# VU-Meter.net
KiCad netlist of a schematic drawn in EAGLE
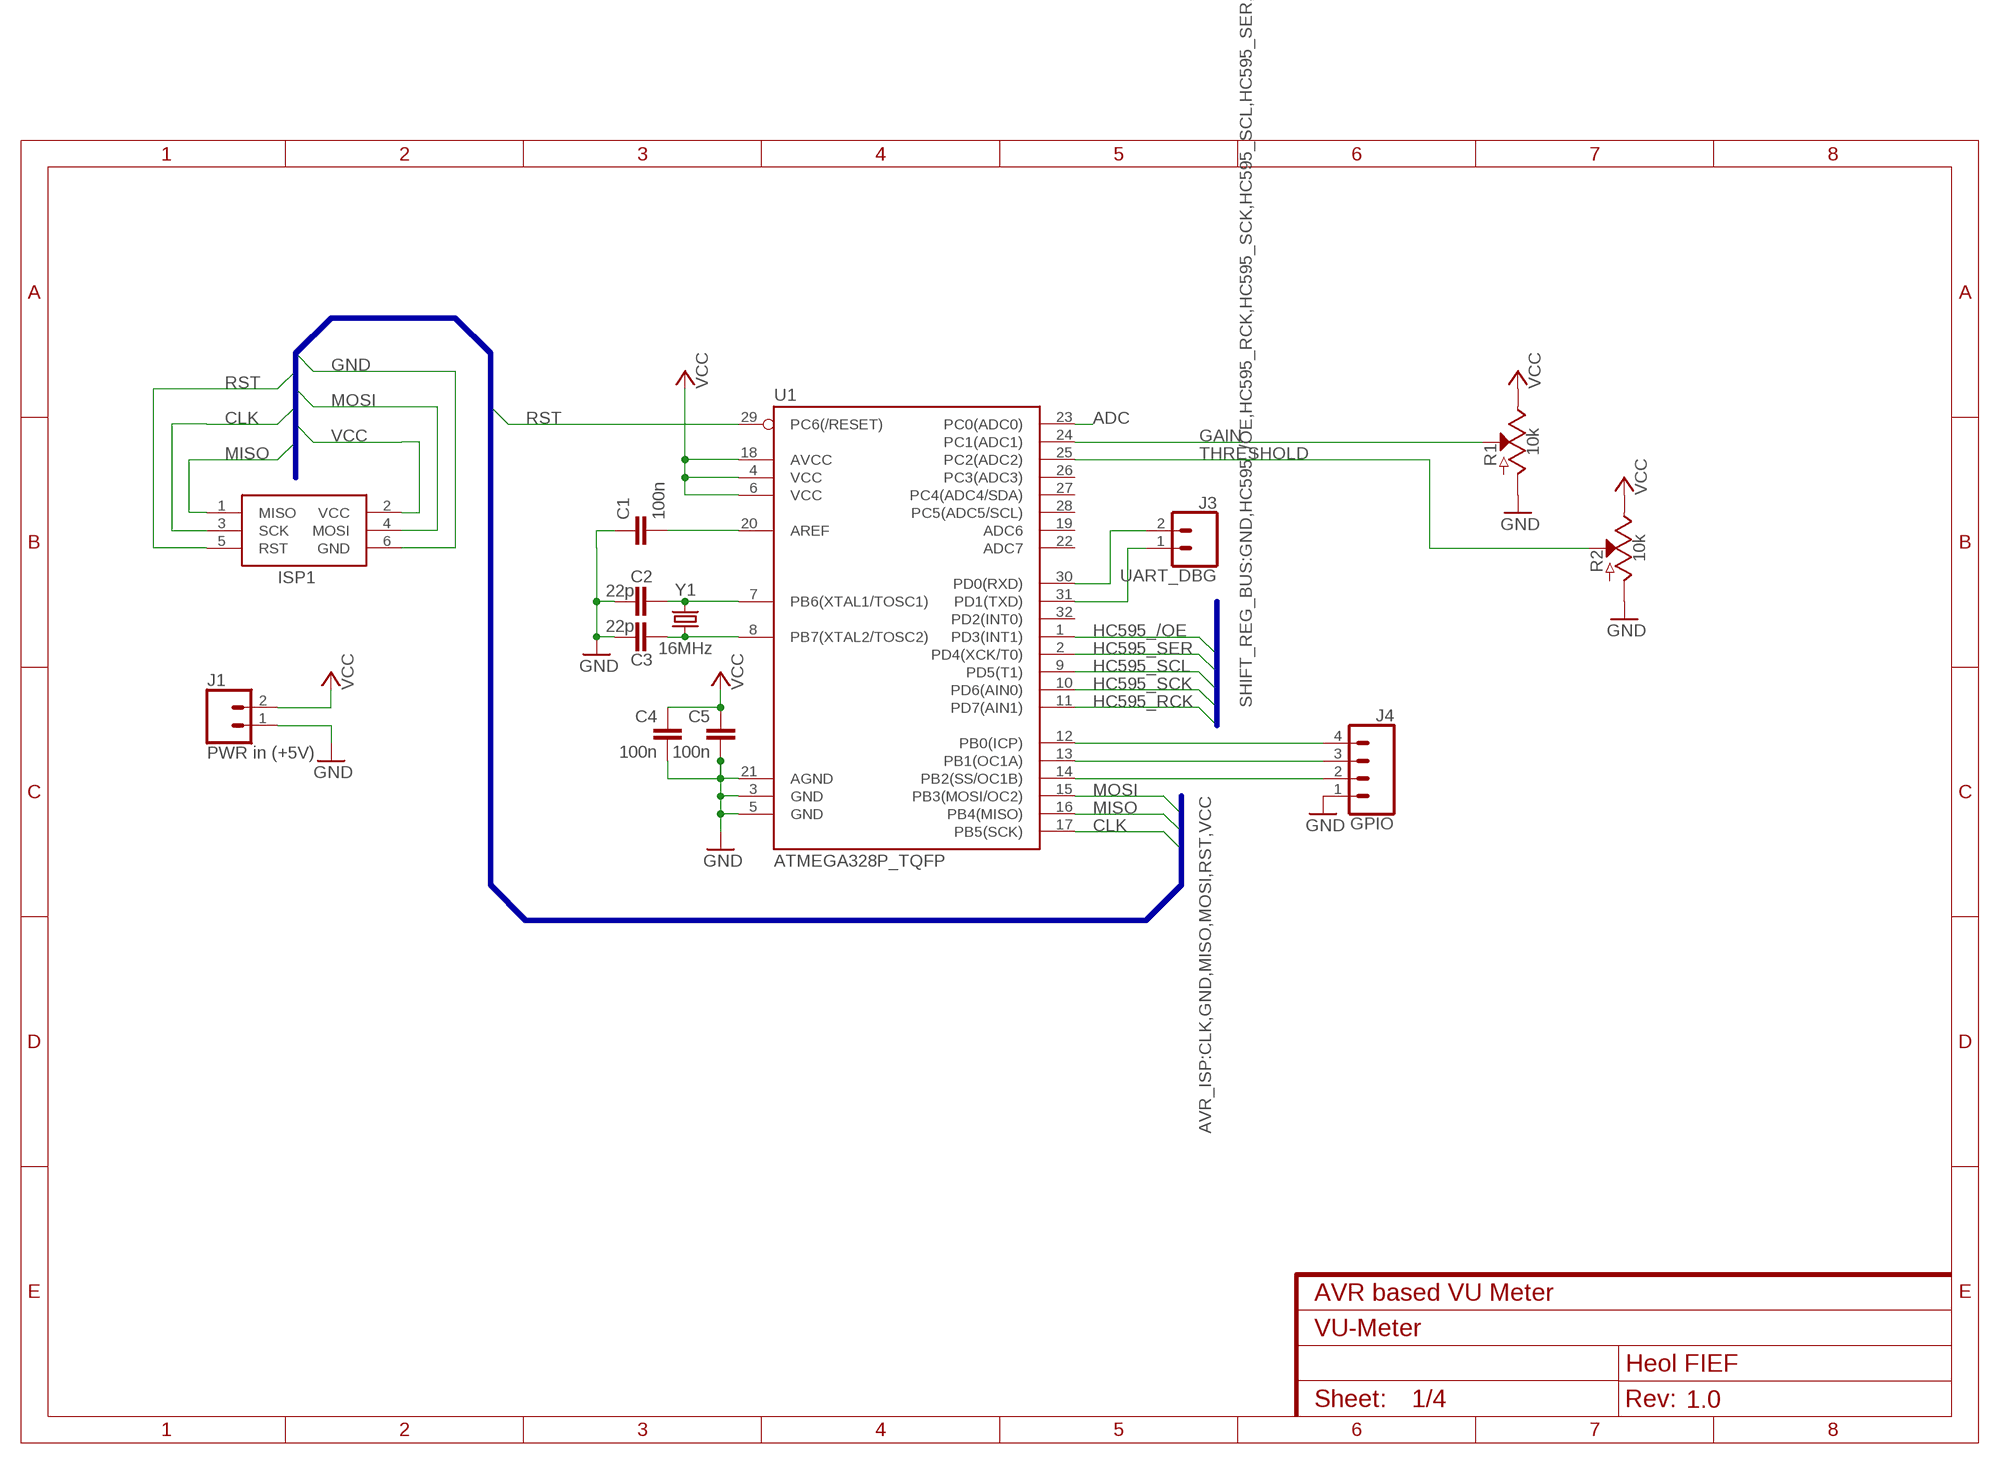
[diagram p0: schematic, sheet 1]
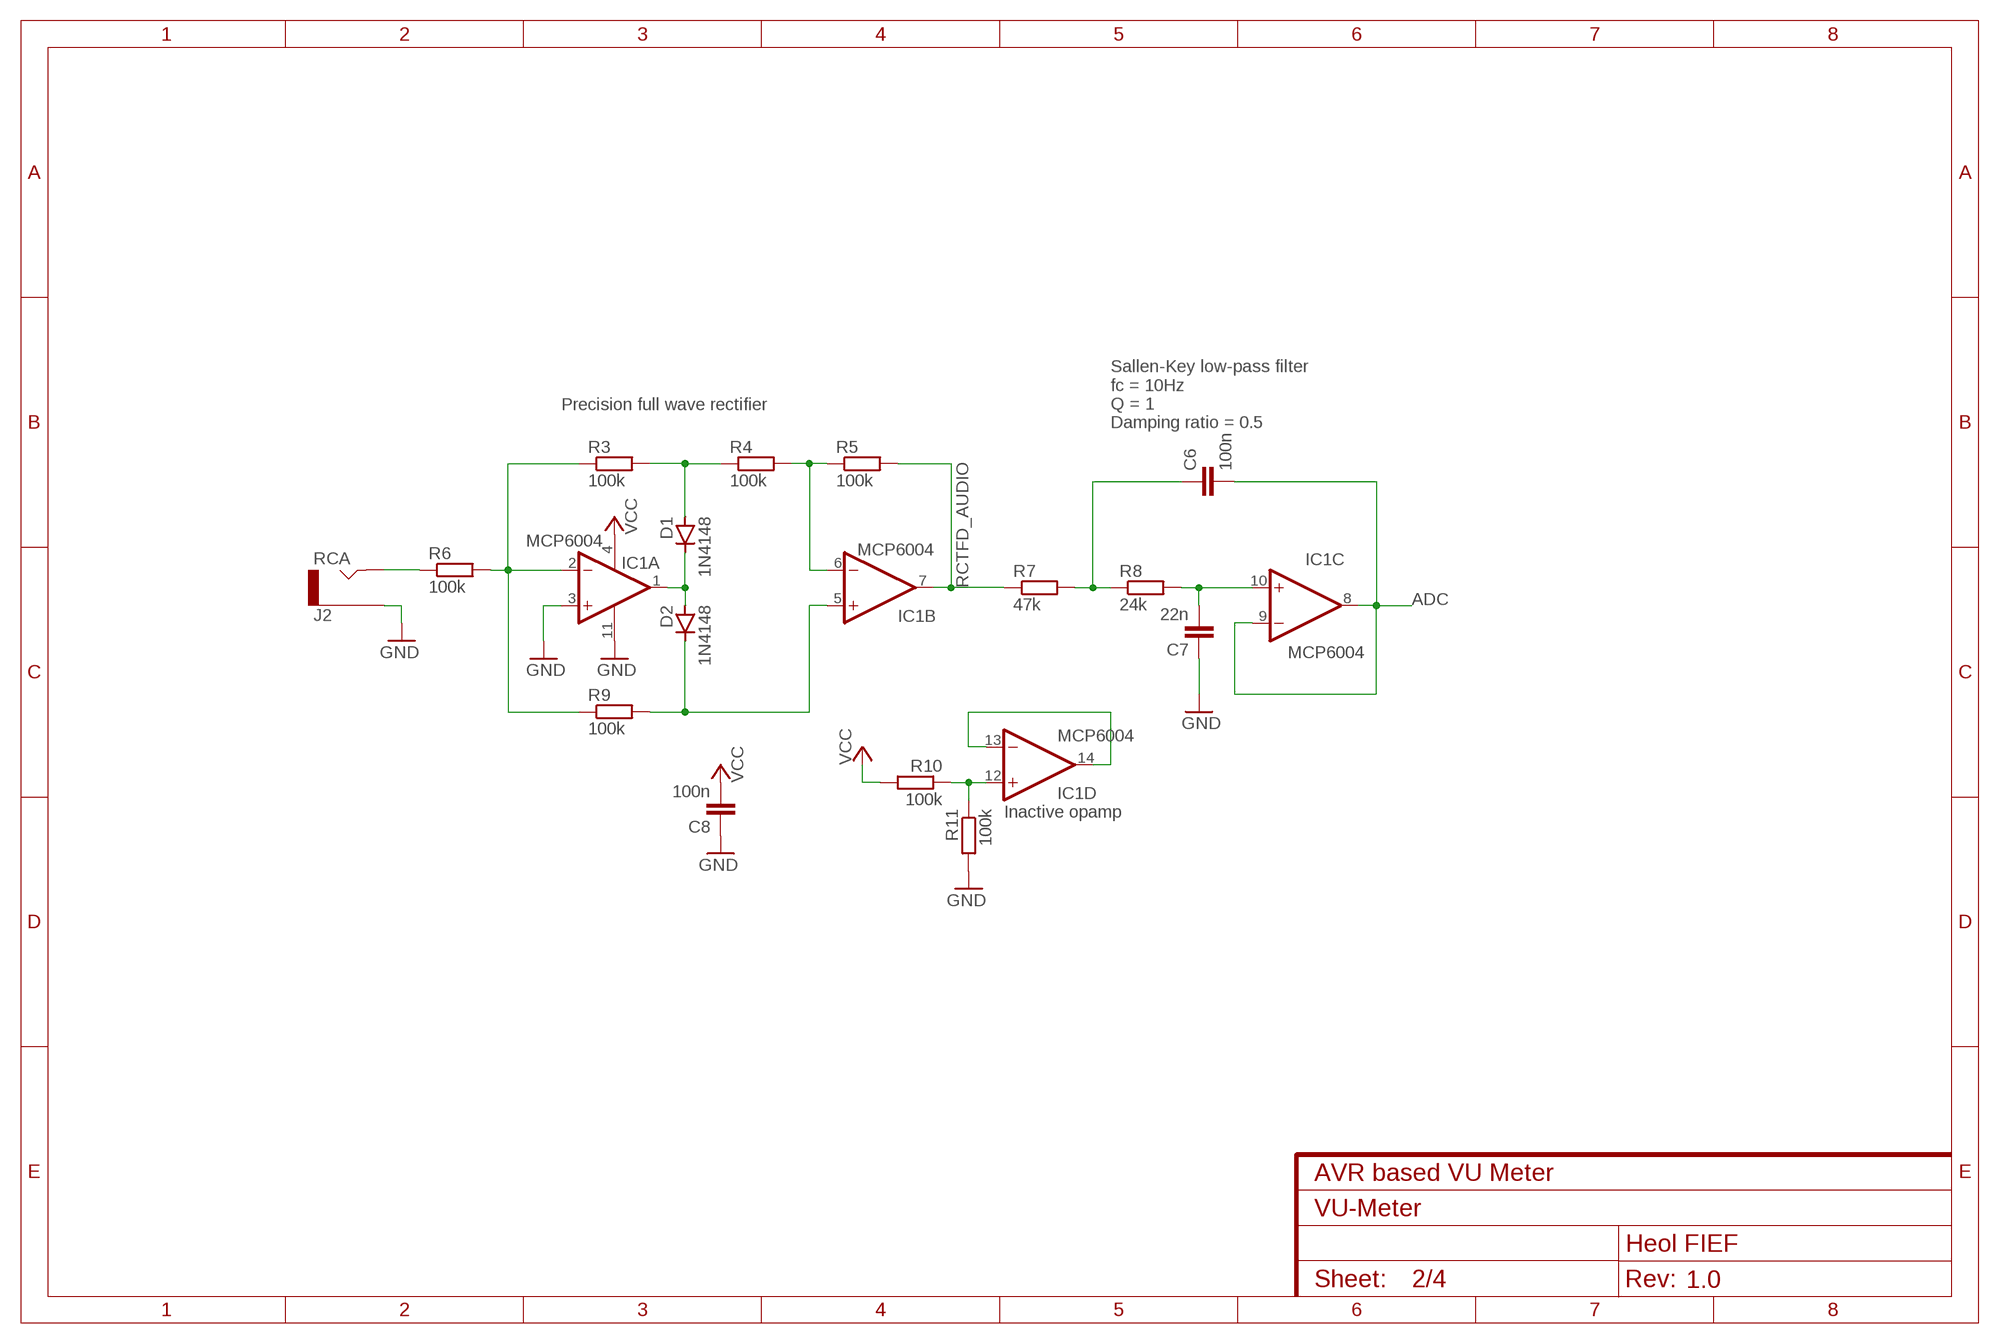
[diagram p1: schematic, sheet 2]
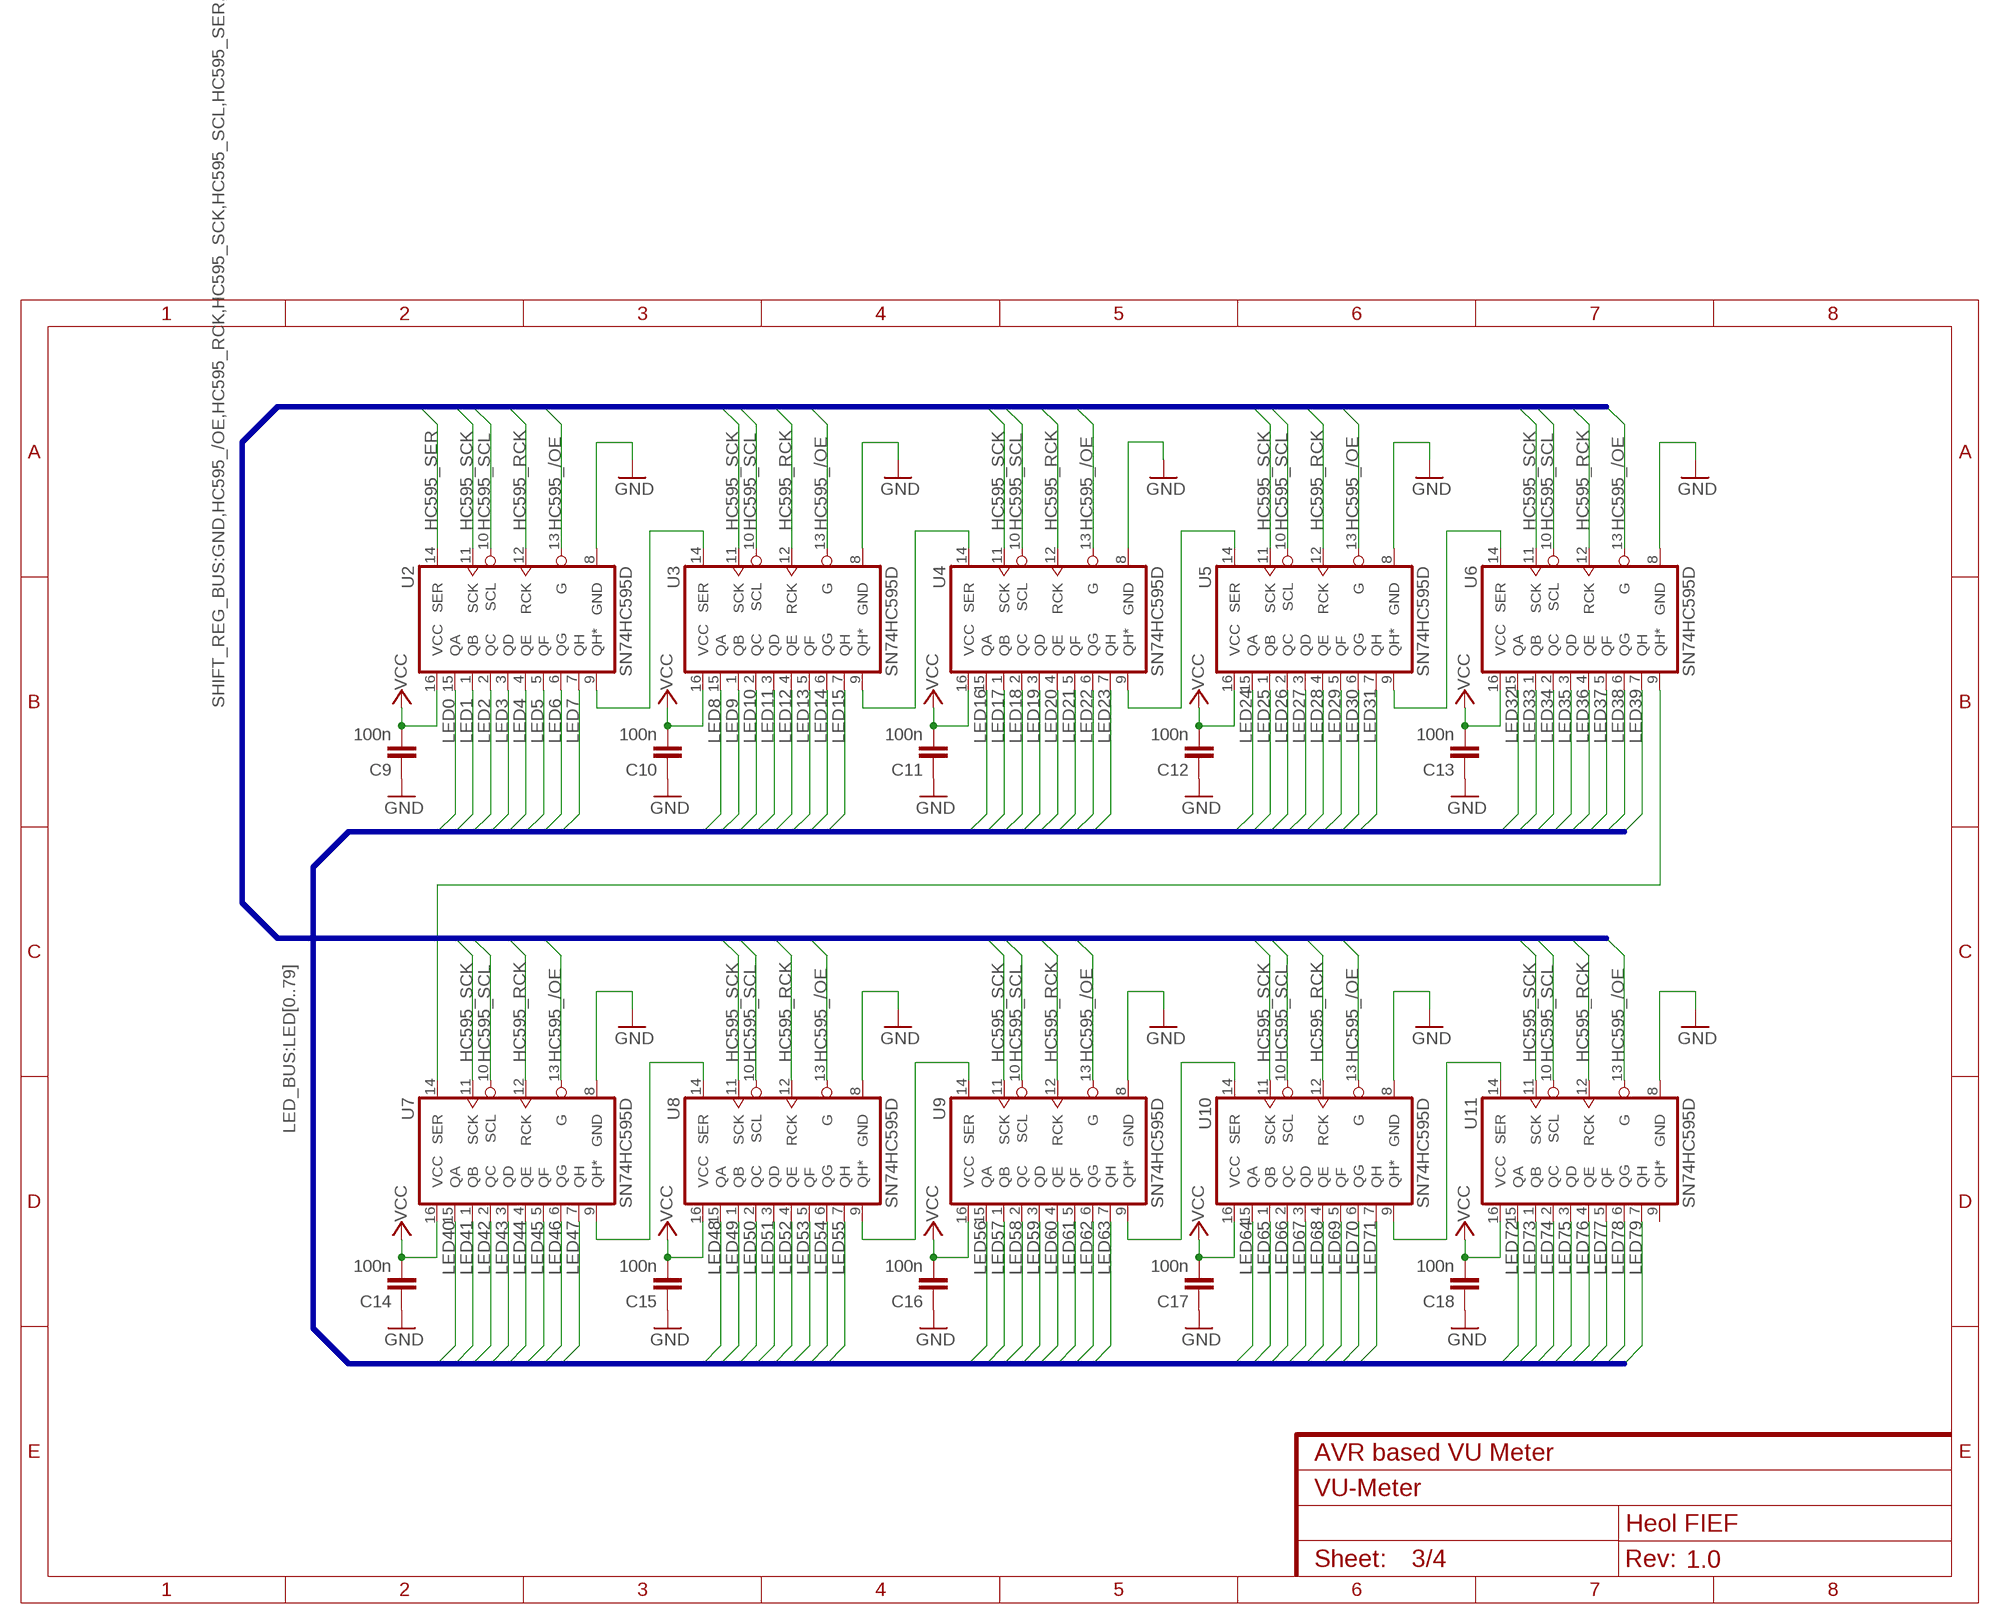
[diagram p2: schematic, sheet 3]
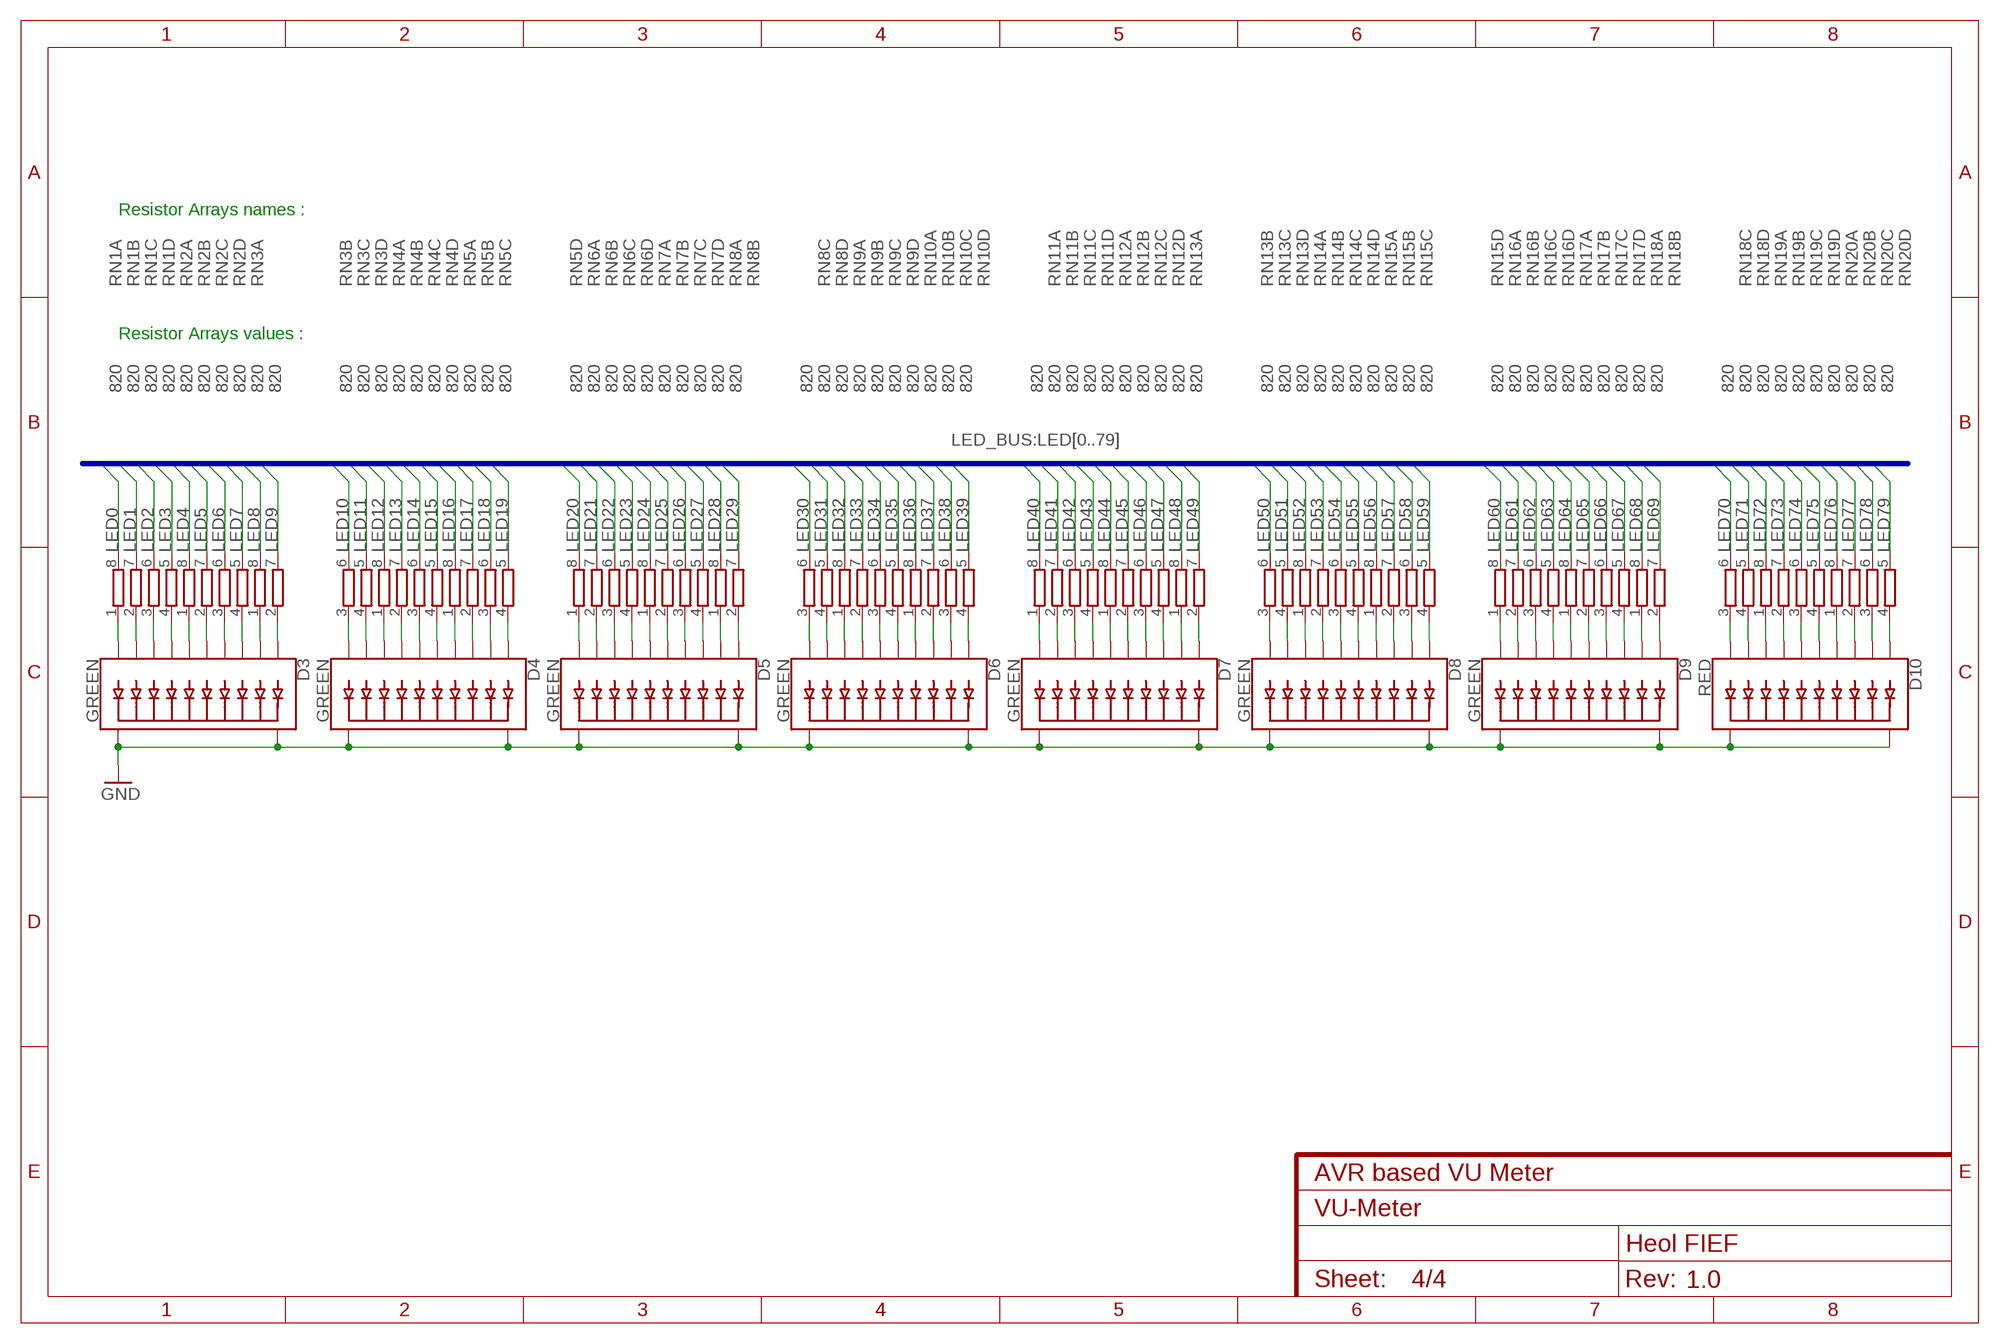
[diagram p3: schematic, sheet 4]

(export (version "E")
  (design (tool "Eeschema 10.0.6"))
  (components
    (comp (ref "C9")
      (value "100n")
      (footprint "eagle-import:C0805")
      (libsource (lib "eagle-import") (part "C-EUC0805"))
    )
    (comp (ref "C10")
      (value "100n")
      (footprint "eagle-import:C0805")
      (libsource (lib "eagle-import") (part "C-EUC0805"))
    )
    (comp (ref "C11")
      (value "100n")
      (footprint "eagle-import:C0805")
      (libsource (lib "eagle-import") (part "C-EUC0805"))
    )
    (comp (ref "C12")
      (value "100n")
      (footprint "eagle-import:C0805")
      (libsource (lib "eagle-import") (part "C-EUC0805"))
    )
    (comp (ref "C13")
      (value "100n")
      (footprint "eagle-import:C0805")
      (libsource (lib "eagle-import") (part "C-EUC0805"))
    )
    (comp (ref "C14")
      (value "100n")
      (footprint "eagle-import:C0805")
      (libsource (lib "eagle-import") (part "C-EUC0805"))
    )
    (comp (ref "C15")
      (value "100n")
      (footprint "eagle-import:C0805")
      (libsource (lib "eagle-import") (part "C-EUC0805"))
    )
    (comp (ref "C16")
      (value "100n")
      (footprint "eagle-import:C0805")
      (libsource (lib "eagle-import") (part "C-EUC0805"))
    )
    (comp (ref "C17")
      (value "100n")
      (footprint "eagle-import:C0805")
      (libsource (lib "eagle-import") (part "C-EUC0805"))
    )
    (comp (ref "C18")
      (value "100n")
      (footprint "eagle-import:C0805")
      (libsource (lib "eagle-import") (part "C-EUC0805"))
    )
    (comp (ref "U2")
      (value "SN74HC595D")
      (footprint "eagle-import:SO16")
      (libsource (lib "eagle-import") (part "74595DHC"))
    )
    (comp (ref "U3")
      (value "SN74HC595D")
      (footprint "eagle-import:SO16")
      (libsource (lib "eagle-import") (part "74595DHC"))
    )
    (comp (ref "U4")
      (value "SN74HC595D")
      (footprint "eagle-import:SO16")
      (libsource (lib "eagle-import") (part "74595DHC"))
    )
    (comp (ref "U5")
      (value "SN74HC595D")
      (footprint "eagle-import:SO16")
      (libsource (lib "eagle-import") (part "74595DHC"))
    )
    (comp (ref "U6")
      (value "SN74HC595D")
      (footprint "eagle-import:SO16")
      (libsource (lib "eagle-import") (part "74595DHC"))
    )
    (comp (ref "U7")
      (value "SN74HC595D")
      (footprint "eagle-import:SO16")
      (libsource (lib "eagle-import") (part "74595DHC"))
    )
    (comp (ref "U8")
      (value "SN74HC595D")
      (footprint "eagle-import:SO16")
      (libsource (lib "eagle-import") (part "74595DHC"))
    )
    (comp (ref "U9")
      (value "SN74HC595D")
      (footprint "eagle-import:SO16")
      (libsource (lib "eagle-import") (part "74595DHC"))
    )
    (comp (ref "U10")
      (value "SN74HC595D")
      (footprint "eagle-import:SO16")
      (libsource (lib "eagle-import") (part "74595DHC"))
    )
    (comp (ref "U11")
      (value "SN74HC595D")
      (footprint "eagle-import:SO16")
      (libsource (lib "eagle-import") (part "74595DHC"))
    )
    (comp (ref "D3")
      (value "GREEN")
      (footprint "eagle-import:LED_BARGRAPH_OFFBOARD_RIGHT_ANGLE")
      (libsource (lib "eagle-import") (part "LED_BARGRAPH_OFFBOARDLED_BARGRAPH_OFFBOARD"))
    )
    (comp (ref "D4")
      (value "GREEN")
      (footprint "eagle-import:LED_BARGRAPH_OFFBOARD_RIGHT_ANGLE")
      (libsource (lib "eagle-import") (part "LED_BARGRAPH_OFFBOARDLED_BARGRAPH_OFFBOARD"))
    )
    (comp (ref "D5")
      (value "GREEN")
      (footprint "eagle-import:LED_BARGRAPH_OFFBOARD_RIGHT_ANGLE")
      (libsource (lib "eagle-import") (part "LED_BARGRAPH_OFFBOARDLED_BARGRAPH_OFFBOARD"))
    )
    (comp (ref "D6")
      (value "GREEN")
      (footprint "eagle-import:LED_BARGRAPH_OFFBOARD_RIGHT_ANGLE")
      (libsource (lib "eagle-import") (part "LED_BARGRAPH_OFFBOARDLED_BARGRAPH_OFFBOARD"))
    )
    (comp (ref "D7")
      (value "GREEN")
      (footprint "eagle-import:LED_BARGRAPH_OFFBOARD_RIGHT_ANGLE")
      (libsource (lib "eagle-import") (part "LED_BARGRAPH_OFFBOARDLED_BARGRAPH_OFFBOARD"))
    )
    (comp (ref "D8")
      (value "GREEN")
      (footprint "eagle-import:LED_BARGRAPH_OFFBOARD_RIGHT_ANGLE")
      (libsource (lib "eagle-import") (part "LED_BARGRAPH_OFFBOARDLED_BARGRAPH_OFFBOARD"))
    )
    (comp (ref "D9")
      (value "GREEN")
      (footprint "eagle-import:LED_BARGRAPH_OFFBOARD_RIGHT_ANGLE")
      (libsource (lib "eagle-import") (part "LED_BARGRAPH_OFFBOARDLED_BARGRAPH_OFFBOARD"))
    )
    (comp (ref "D10")
      (value "RED")
      (footprint "eagle-import:LED_BARGRAPH_OFFBOARD_RIGHT_ANGLE")
      (libsource (lib "eagle-import") (part "LED_BARGRAPH_OFFBOARDLED_BARGRAPH_OFFBOARD"))
    )
    (comp (ref "RN1")
      (value "820")
      (footprint "eagle-import:0603-ARC")
      (libsource (lib "eagle-import") (part "4R-N0603-ARC"))
    )
    (comp (ref "RN2")
      (value "820")
      (footprint "eagle-import:0603-ARC")
      (libsource (lib "eagle-import") (part "4R-N0603-ARC"))
    )
    (comp (ref "RN3")
      (value "820")
      (footprint "eagle-import:0603-ARC")
      (libsource (lib "eagle-import") (part "4R-N0603-ARC"))
    )
    (comp (ref "RN4")
      (value "820")
      (footprint "eagle-import:0603-ARC")
      (libsource (lib "eagle-import") (part "4R-N0603-ARC"))
    )
    (comp (ref "RN5")
      (value "820")
      (footprint "eagle-import:0603-ARC")
      (libsource (lib "eagle-import") (part "4R-N0603-ARC"))
    )
    (comp (ref "RN6")
      (value "820")
      (footprint "eagle-import:0603-ARC")
      (libsource (lib "eagle-import") (part "4R-N0603-ARC"))
    )
    (comp (ref "RN7")
      (value "820")
      (footprint "eagle-import:0603-ARC")
      (libsource (lib "eagle-import") (part "4R-N0603-ARC"))
    )
    (comp (ref "RN8")
      (value "820")
      (footprint "eagle-import:0603-ARC")
      (libsource (lib "eagle-import") (part "4R-N0603-ARC"))
    )
    (comp (ref "RN9")
      (value "820")
      (footprint "eagle-import:0603-ARC")
      (libsource (lib "eagle-import") (part "4R-N0603-ARC"))
    )
    (comp (ref "RN10")
      (value "820")
      (footprint "eagle-import:0603-ARC")
      (libsource (lib "eagle-import") (part "4R-N0603-ARC"))
    )
    (comp (ref "RN11")
      (value "820")
      (footprint "eagle-import:0603-ARC")
      (libsource (lib "eagle-import") (part "4R-N0603-ARC"))
    )
    (comp (ref "RN12")
      (value "820")
      (footprint "eagle-import:0603-ARC")
      (libsource (lib "eagle-import") (part "4R-N0603-ARC"))
    )
    (comp (ref "RN13")
      (value "820")
      (footprint "eagle-import:0603-ARC")
      (libsource (lib "eagle-import") (part "4R-N0603-ARC"))
    )
    (comp (ref "RN14")
      (value "820")
      (footprint "eagle-import:0603-ARC")
      (libsource (lib "eagle-import") (part "4R-N0603-ARC"))
    )
    (comp (ref "RN15")
      (value "820")
      (footprint "eagle-import:0603-ARC")
      (libsource (lib "eagle-import") (part "4R-N0603-ARC"))
    )
    (comp (ref "RN16")
      (value "820")
      (footprint "eagle-import:0603-ARC")
      (libsource (lib "eagle-import") (part "4R-N0603-ARC"))
    )
    (comp (ref "RN17")
      (value "820")
      (footprint "eagle-import:0603-ARC")
      (libsource (lib "eagle-import") (part "4R-N0603-ARC"))
    )
    (comp (ref "RN18")
      (value "820")
      (footprint "eagle-import:0603-ARC")
      (libsource (lib "eagle-import") (part "4R-N0603-ARC"))
    )
    (comp (ref "RN19")
      (value "820")
      (footprint "eagle-import:0603-ARC")
      (libsource (lib "eagle-import") (part "4R-N0603-ARC"))
    )
    (comp (ref "RN20")
      (value "820")
      (footprint "eagle-import:0603-ARC")
      (libsource (lib "eagle-import") (part "4R-N0603-ARC"))
    )
    (comp (ref "C6")
      (value "100n")
      (footprint "eagle-import:C0805")
      (libsource (lib "eagle-import") (part "C-EUC0805"))
    )
    (comp (ref "C7")
      (value "22n")
      (footprint "eagle-import:C0805")
      (libsource (lib "eagle-import") (part "C-EUC0805"))
    )
    (comp (ref "C8")
      (value "100n")
      (footprint "eagle-import:C0805")
      (libsource (lib "eagle-import") (part "C-EUC0805"))
    )
    (comp (ref "D1")
      (value "1N4148")
      (footprint "eagle-import:SOD80")
      (libsource (lib "eagle-import") (part "D-SOD-80"))
    )
    (comp (ref "D2")
      (value "1N4148")
      (footprint "eagle-import:SOD80")
      (libsource (lib "eagle-import") (part "D-SOD-80"))
    )
    (comp (ref "IC1")
      (value "MCP6004")
      (footprint "eagle-import:SO14")
      (libsource (lib "eagle-import") (part "QUAD_OPAMPD"))
    )
    (comp (ref "J2")
      (value "RCA")
      (footprint "eagle-import:1X02")
      (libsource (lib "eagle-import") (part "MONO_JACK_OFFBOARD"))
    )
    (comp (ref "R3")
      (value "100k")
      (footprint "eagle-import:R0805")
      (libsource (lib "eagle-import") (part "R-EU_R0805"))
    )
    (comp (ref "R4")
      (value "100k")
      (footprint "eagle-import:R0805")
      (libsource (lib "eagle-import") (part "R-EU_R0805"))
    )
    (comp (ref "R5")
      (value "100k")
      (footprint "eagle-import:R0805")
      (libsource (lib "eagle-import") (part "R-EU_R0805"))
    )
    (comp (ref "R6")
      (value "100k")
      (footprint "eagle-import:R0805")
      (libsource (lib "eagle-import") (part "R-EU_R0805"))
    )
    (comp (ref "R7")
      (value "47k")
      (footprint "eagle-import:R0805")
      (libsource (lib "eagle-import") (part "R-EU_R0805"))
    )
    (comp (ref "R8")
      (value "24k")
      (footprint "eagle-import:R0805")
      (libsource (lib "eagle-import") (part "R-EU_R0805"))
    )
    (comp (ref "R9")
      (value "100k")
      (footprint "eagle-import:R0805")
      (libsource (lib "eagle-import") (part "R-EU_R0805"))
    )
    (comp (ref "R10")
      (value "100k")
      (footprint "eagle-import:R0805")
      (libsource (lib "eagle-import") (part "R-EU_R0805"))
    )
    (comp (ref "R11")
      (value "100k")
      (footprint "eagle-import:R0805")
      (libsource (lib "eagle-import") (part "R-EU_R0805"))
    )
    (comp (ref "C1")
      (value "100n")
      (footprint "eagle-import:C0805")
      (libsource (lib "eagle-import") (part "C-EUC0805"))
    )
    (comp (ref "C2")
      (value "22p")
      (footprint "eagle-import:C0805")
      (libsource (lib "eagle-import") (part "C-EUC0805"))
    )
    (comp (ref "C3")
      (value "22p")
      (footprint "eagle-import:C0805")
      (libsource (lib "eagle-import") (part "C-EUC0805"))
    )
    (comp (ref "C4")
      (value "100n")
      (footprint "eagle-import:C0805")
      (libsource (lib "eagle-import") (part "C-EUC0805"))
    )
    (comp (ref "C5")
      (value "100n")
      (footprint "eagle-import:C0805")
      (libsource (lib "eagle-import") (part "C-EUC0805"))
    )
    (comp (ref "ISP1")
      (value "AVRISP-6")
      (footprint "eagle-import:AVRISP")
      (libsource (lib "eagle-import") (part "AVRISP-6"))
    )
    (comp (ref "J1")
      (value "PWR in (+5V)")
      (footprint "eagle-import:1X02")
      (libsource (lib "eagle-import") (part "CONN_02"))
    )
    (comp (ref "J3")
      (value "UART_DBG")
      (footprint "eagle-import:1X02")
      (libsource (lib "eagle-import") (part "CONN_02"))
    )
    (comp (ref "J4")
      (value "GPIO")
      (footprint "eagle-import:1X04")
      (libsource (lib "eagle-import") (part "CONN_04"))
    )
    (comp (ref "R1")
      (value "10k")
      (footprint "eagle-import:1X03")
      (libsource (lib "eagle-import") (part "POT_OFFBOARD"))
    )
    (comp (ref "R2")
      (value "10k")
      (footprint "eagle-import:1X03")
      (libsource (lib "eagle-import") (part "POT_OFFBOARD"))
    )
    (comp (ref "U1")
      (value "ATMEGA328P_TQFP")
      (footprint "eagle-import:TQFP32-08")
      (libsource (lib "eagle-import") (part "ATMEGA328P_TQFP"))
    )
    (comp (ref "Y1")
      (value "16MHz")
      (footprint "eagle-import:CRYSTAL-SMD-3.2X2.5MM")
      (libsource (lib "eagle-import") (part "CRYSTALSMD-3.2X2.5"))
    )
  )
  (nets
    (net (code "169") (name "ADC") (class "Default")
      (node (ref "C6") (pin "2") (pinfunction "2_2") (pintype "passive"))
      (node (ref "IC1") (pin "8") (pinfunction "OUT_8") (pintype "output"))
      (node (ref "IC1") (pin "9") (pinfunction "-IN_9") (pintype "input"))
      (node (ref "U1") (pin "23") (pinfunction "PC0(ADC0)_23") (pintype "bidirectional"))
    )
    (net (code "170") (name "CLK") (class "Default")
      (node (ref "ISP1") (pin "3") (pinfunction "SCK_3") (pintype "output"))
      (node (ref "U1") (pin "17") (pinfunction "PB5(SCK)_17") (pintype "bidirectional"))
    )
    (net (code "171") (name "GAIN") (class "Default")
      (node (ref "R1") (pin "2") (pinfunction "S_2") (pintype "passive"))
      (node (ref "U1") (pin "24") (pinfunction "PC1(ADC1)_24") (pintype "bidirectional"))
    )
    (net (code "172") (name "GND") (class "Default")
      (node (ref "C1") (pin "1") (pinfunction "1_1") (pintype "passive"))
      (node (ref "C10") (pin "1") (pinfunction "1_1") (pintype "passive"))
      (node (ref "C11") (pin "1") (pinfunction "1_1") (pintype "passive"))
      (node (ref "C12") (pin "1") (pinfunction "1_1") (pintype "passive"))
      (node (ref "C13") (pin "1") (pinfunction "1_1") (pintype "passive"))
      (node (ref "C14") (pin "1") (pinfunction "1_1") (pintype "passive"))
      (node (ref "C15") (pin "1") (pinfunction "1_1") (pintype "passive"))
      (node (ref "C16") (pin "1") (pinfunction "1_1") (pintype "passive"))
      (node (ref "C17") (pin "1") (pinfunction "1_1") (pintype "passive"))
      (node (ref "C18") (pin "1") (pinfunction "1_1") (pintype "passive"))
      (node (ref "C2") (pin "1") (pinfunction "1_1") (pintype "passive"))
      (node (ref "C3") (pin "1") (pinfunction "1_1") (pintype "passive"))
      (node (ref "C4") (pin "2") (pinfunction "2_2") (pintype "passive"))
      (node (ref "C5") (pin "2") (pinfunction "2_2") (pintype "passive"))
      (node (ref "C7") (pin "1") (pinfunction "1_1") (pintype "passive"))
      (node (ref "C8") (pin "1") (pinfunction "1_1") (pintype "passive"))
      (node (ref "C9") (pin "1") (pinfunction "1_1") (pintype "passive"))
      (node (ref "D10") (pin "P$11") (pinfunction "C_P$11") (pintype "passive"))
      (node (ref "D10") (pin "P$12") (pinfunction "C1_P$12") (pintype "passive"))
      (node (ref "D3") (pin "P$11") (pinfunction "C_P$11") (pintype "passive"))
      (node (ref "D3") (pin "P$12") (pinfunction "C1_P$12") (pintype "passive"))
      (node (ref "D4") (pin "P$11") (pinfunction "C_P$11") (pintype "passive"))
      (node (ref "D4") (pin "P$12") (pinfunction "C1_P$12") (pintype "passive"))
      (node (ref "D5") (pin "P$11") (pinfunction "C_P$11") (pintype "passive"))
      (node (ref "D5") (pin "P$12") (pinfunction "C1_P$12") (pintype "passive"))
      (node (ref "D6") (pin "P$11") (pinfunction "C_P$11") (pintype "passive"))
      (node (ref "D6") (pin "P$12") (pinfunction "C1_P$12") (pintype "passive"))
      (node (ref "D7") (pin "P$11") (pinfunction "C_P$11") (pintype "passive"))
      (node (ref "D7") (pin "P$12") (pinfunction "C1_P$12") (pintype "passive"))
      (node (ref "D8") (pin "P$11") (pinfunction "C_P$11") (pintype "passive"))
      (node (ref "D8") (pin "P$12") (pinfunction "C1_P$12") (pintype "passive"))
      (node (ref "D9") (pin "P$11") (pinfunction "C_P$11") (pintype "passive"))
      (node (ref "D9") (pin "P$12") (pinfunction "C1_P$12") (pintype "passive"))
      (node (ref "IC1") (pin "11") (pinfunction "V-_11") (pintype "power_in"))
      (node (ref "IC1") (pin "3") (pinfunction "+IN_3") (pintype "input"))
      (node (ref "ISP1") (pin "6") (pinfunction "GND_6") (pintype "power_in"))
      (node (ref "J1") (pin "1") (pinfunction "1_1") (pintype "passive"))
      (node (ref "J2") (pin "2") (pinfunction "SLEEVE_2") (pintype "bidirectional"))
      (node (ref "J4") (pin "1") (pinfunction "1_1") (pintype "passive"))
      (node (ref "R1") (pin "3") (pinfunction "A_3") (pintype "passive"))
      (node (ref "R11") (pin "2") (pinfunction "2_2") (pintype "passive"))
      (node (ref "R2") (pin "3") (pinfunction "A_3") (pintype "passive"))
      (node (ref "U1") (pin "21") (pinfunction "AGND_21") (pintype "bidirectional"))
      (node (ref "U1") (pin "3") (pinfunction "GND_3") (pintype "bidirectional"))
      (node (ref "U1") (pin "5") (pinfunction "GND_5") (pintype "bidirectional"))
      (node (ref "U10") (pin "8") (pinfunction "GND_8") (pintype "power_in"))
      (node (ref "U11") (pin "8") (pinfunction "GND_8") (pintype "power_in"))
      (node (ref "U2") (pin "8") (pinfunction "GND_8") (pintype "power_in"))
      (node (ref "U3") (pin "8") (pinfunction "GND_8") (pintype "power_in"))
      (node (ref "U4") (pin "8") (pinfunction "GND_8") (pintype "power_in"))
      (node (ref "U5") (pin "8") (pinfunction "GND_8") (pintype "power_in"))
      (node (ref "U6") (pin "8") (pinfunction "GND_8") (pintype "power_in"))
      (node (ref "U7") (pin "8") (pinfunction "GND_8") (pintype "power_in"))
      (node (ref "U8") (pin "8") (pinfunction "GND_8") (pintype "power_in"))
      (node (ref "U9") (pin "8") (pinfunction "GND_8") (pintype "power_in"))
    )
    (net (code "173") (name "HC595_RCK") (class "Default")
      (node (ref "U1") (pin "11") (pinfunction "PD7(AIN1)_11") (pintype "bidirectional"))
      (node (ref "U10") (pin "12") (pinfunction "RCK_12") (pintype "input"))
      (node (ref "U11") (pin "12") (pinfunction "RCK_12") (pintype "input"))
      (node (ref "U2") (pin "12") (pinfunction "RCK_12") (pintype "input"))
      (node (ref "U3") (pin "12") (pinfunction "RCK_12") (pintype "input"))
      (node (ref "U4") (pin "12") (pinfunction "RCK_12") (pintype "input"))
      (node (ref "U5") (pin "12") (pinfunction "RCK_12") (pintype "input"))
      (node (ref "U6") (pin "12") (pinfunction "RCK_12") (pintype "input"))
      (node (ref "U7") (pin "12") (pinfunction "RCK_12") (pintype "input"))
      (node (ref "U8") (pin "12") (pinfunction "RCK_12") (pintype "input"))
      (node (ref "U9") (pin "12") (pinfunction "RCK_12") (pintype "input"))
    )
    (net (code "174") (name "HC595_SCK") (class "Default")
      (node (ref "U1") (pin "10") (pinfunction "PD6(AIN0)_10") (pintype "bidirectional"))
      (node (ref "U10") (pin "11") (pinfunction "SCK_11") (pintype "input"))
      (node (ref "U11") (pin "11") (pinfunction "SCK_11") (pintype "input"))
      (node (ref "U2") (pin "11") (pinfunction "SCK_11") (pintype "input"))
      (node (ref "U3") (pin "11") (pinfunction "SCK_11") (pintype "input"))
      (node (ref "U4") (pin "11") (pinfunction "SCK_11") (pintype "input"))
      (node (ref "U5") (pin "11") (pinfunction "SCK_11") (pintype "input"))
      (node (ref "U6") (pin "11") (pinfunction "SCK_11") (pintype "input"))
      (node (ref "U7") (pin "11") (pinfunction "SCK_11") (pintype "input"))
      (node (ref "U8") (pin "11") (pinfunction "SCK_11") (pintype "input"))
      (node (ref "U9") (pin "11") (pinfunction "SCK_11") (pintype "input"))
    )
    (net (code "175") (name "HC595_SCL") (class "Default")
      (node (ref "U1") (pin "9") (pinfunction "PD5(T1)_9") (pintype "bidirectional"))
      (node (ref "U10") (pin "10") (pinfunction "SCL_10") (pintype "input"))
      (node (ref "U11") (pin "10") (pinfunction "SCL_10") (pintype "input"))
      (node (ref "U2") (pin "10") (pinfunction "SCL_10") (pintype "input"))
      (node (ref "U3") (pin "10") (pinfunction "SCL_10") (pintype "input"))
      (node (ref "U4") (pin "10") (pinfunction "SCL_10") (pintype "input"))
      (node (ref "U5") (pin "10") (pinfunction "SCL_10") (pintype "input"))
      (node (ref "U6") (pin "10") (pinfunction "SCL_10") (pintype "input"))
      (node (ref "U7") (pin "10") (pinfunction "SCL_10") (pintype "input"))
      (node (ref "U8") (pin "10") (pinfunction "SCL_10") (pintype "input"))
      (node (ref "U9") (pin "10") (pinfunction "SCL_10") (pintype "input"))
    )
    (net (code "176") (name "HC595_SER") (class "Default")
      (node (ref "U1") (pin "2") (pinfunction "PD4(XCK/T0)_2") (pintype "bidirectional"))
      (node (ref "U2") (pin "14") (pinfunction "SER_14") (pintype "input"))
    )
    (net (code "177") (name "HC595_{slash}OE") (class "Default")
      (node (ref "U1") (pin "1") (pinfunction "PD3(INT1)_1") (pintype "bidirectional"))
      (node (ref "U10") (pin "13") (pinfunction "G_13") (pintype "input"))
      (node (ref "U11") (pin "13") (pinfunction "G_13") (pintype "input"))
      (node (ref "U2") (pin "13") (pinfunction "G_13") (pintype "input"))
      (node (ref "U3") (pin "13") (pinfunction "G_13") (pintype "input"))
      (node (ref "U4") (pin "13") (pinfunction "G_13") (pintype "input"))
      (node (ref "U5") (pin "13") (pinfunction "G_13") (pintype "input"))
      (node (ref "U6") (pin "13") (pinfunction "G_13") (pintype "input"))
      (node (ref "U7") (pin "13") (pinfunction "G_13") (pintype "input"))
      (node (ref "U8") (pin "13") (pinfunction "G_13") (pintype "input"))
      (node (ref "U9") (pin "13") (pinfunction "G_13") (pintype "input"))
    )
    (net (code "178") (name "LED0") (class "Default")
      (node (ref "RN1") (pin "8") (pinfunction "2_8") (pintype "passive"))
      (node (ref "U2") (pin "15") (pinfunction "QA_15") (pintype "tri_state"))
    )
    (net (code "179") (name "LED1") (class "Default")
      (node (ref "RN1") (pin "7") (pinfunction "2_7") (pintype "passive"))
      (node (ref "U2") (pin "1") (pinfunction "QB_1") (pintype "tri_state"))
    )
    (net (code "180") (name "LED2") (class "Default")
      (node (ref "RN1") (pin "6") (pinfunction "2_6") (pintype "passive"))
      (node (ref "U2") (pin "2") (pinfunction "QC_2") (pintype "tri_state"))
    )
    (net (code "181") (name "LED3") (class "Default")
      (node (ref "RN1") (pin "5") (pinfunction "2_5") (pintype "passive"))
      (node (ref "U2") (pin "3") (pinfunction "QD_3") (pintype "tri_state"))
    )
    (net (code "182") (name "LED4") (class "Default")
      (node (ref "RN2") (pin "8") (pinfunction "2_8") (pintype "passive"))
      (node (ref "U2") (pin "4") (pinfunction "QE_4") (pintype "tri_state"))
    )
    (net (code "183") (name "LED5") (class "Default")
      (node (ref "RN2") (pin "7") (pinfunction "2_7") (pintype "passive"))
      (node (ref "U2") (pin "5") (pinfunction "QF_5") (pintype "tri_state"))
    )
    (net (code "184") (name "LED6") (class "Default")
      (node (ref "RN2") (pin "6") (pinfunction "2_6") (pintype "passive"))
      (node (ref "U2") (pin "6") (pinfunction "QG_6") (pintype "tri_state"))
    )
    (net (code "185") (name "LED7") (class "Default")
      (node (ref "RN2") (pin "5") (pinfunction "2_5") (pintype "passive"))
      (node (ref "U2") (pin "7") (pinfunction "QH_7") (pintype "tri_state"))
    )
    (net (code "186") (name "LED8") (class "Default")
      (node (ref "RN3") (pin "8") (pinfunction "2_8") (pintype "passive"))
      (node (ref "U3") (pin "15") (pinfunction "QA_15") (pintype "tri_state"))
    )
    (net (code "187") (name "LED9") (class "Default")
      (node (ref "RN3") (pin "7") (pinfunction "2_7") (pintype "passive"))
      (node (ref "U3") (pin "1") (pinfunction "QB_1") (pintype "tri_state"))
    )
    (net (code "188") (name "LED10") (class "Default")
      (node (ref "RN3") (pin "6") (pinfunction "2_6") (pintype "passive"))
      (node (ref "U3") (pin "2") (pinfunction "QC_2") (pintype "tri_state"))
    )
    (net (code "189") (name "LED11") (class "Default")
      (node (ref "RN3") (pin "5") (pinfunction "2_5") (pintype "passive"))
      (node (ref "U3") (pin "3") (pinfunction "QD_3") (pintype "tri_state"))
    )
    (net (code "190") (name "LED12") (class "Default")
      (node (ref "RN4") (pin "8") (pinfunction "2_8") (pintype "passive"))
      (node (ref "U3") (pin "4") (pinfunction "QE_4") (pintype "tri_state"))
    )
    (net (code "191") (name "LED13") (class "Default")
      (node (ref "RN4") (pin "7") (pinfunction "2_7") (pintype "passive"))
      (node (ref "U3") (pin "5") (pinfunction "QF_5") (pintype "tri_state"))
    )
    (net (code "192") (name "LED14") (class "Default")
      (node (ref "RN4") (pin "6") (pinfunction "2_6") (pintype "passive"))
      (node (ref "U3") (pin "6") (pinfunction "QG_6") (pintype "tri_state"))
    )
    (net (code "193") (name "LED15") (class "Default")
      (node (ref "RN4") (pin "5") (pinfunction "2_5") (pintype "passive"))
      (node (ref "U3") (pin "7") (pinfunction "QH_7") (pintype "tri_state"))
    )
    (net (code "194") (name "LED16") (class "Default")
      (node (ref "RN5") (pin "8") (pinfunction "2_8") (pintype "passive"))
      (node (ref "U4") (pin "15") (pinfunction "QA_15") (pintype "tri_state"))
    )
    (net (code "195") (name "LED17") (class "Default")
      (node (ref "RN5") (pin "7") (pinfunction "2_7") (pintype "passive"))
      (node (ref "U4") (pin "1") (pinfunction "QB_1") (pintype "tri_state"))
    )
    (net (code "196") (name "LED18") (class "Default")
      (node (ref "RN5") (pin "6") (pinfunction "2_6") (pintype "passive"))
      (node (ref "U4") (pin "2") (pinfunction "QC_2") (pintype "tri_state"))
    )
    (net (code "197") (name "LED19") (class "Default")
      (node (ref "RN5") (pin "5") (pinfunction "2_5") (pintype "passive"))
      (node (ref "U4") (pin "3") (pinfunction "QD_3") (pintype "tri_state"))
    )
    (net (code "198") (name "LED20") (class "Default")
      (node (ref "RN6") (pin "8") (pinfunction "2_8") (pintype "passive"))
      (node (ref "U4") (pin "4") (pinfunction "QE_4") (pintype "tri_state"))
    )
    (net (code "199") (name "LED21") (class "Default")
      (node (ref "RN6") (pin "7") (pinfunction "2_7") (pintype "passive"))
      (node (ref "U4") (pin "5") (pinfunction "QF_5") (pintype "tri_state"))
    )
    (net (code "200") (name "LED22") (class "Default")
      (node (ref "RN6") (pin "6") (pinfunction "2_6") (pintype "passive"))
      (node (ref "U4") (pin "6") (pinfunction "QG_6") (pintype "tri_state"))
    )
    (net (code "201") (name "LED23") (class "Default")
      (node (ref "RN6") (pin "5") (pinfunction "2_5") (pintype "passive"))
      (node (ref "U4") (pin "7") (pinfunction "QH_7") (pintype "tri_state"))
    )
    (net (code "202") (name "LED24") (class "Default")
      (node (ref "RN7") (pin "8") (pinfunction "2_8") (pintype "passive"))
      (node (ref "U5") (pin "15") (pinfunction "QA_15") (pintype "tri_state"))
    )
    (net (code "203") (name "LED25") (class "Default")
      (node (ref "RN7") (pin "7") (pinfunction "2_7") (pintype "passive"))
      (node (ref "U5") (pin "1") (pinfunction "QB_1") (pintype "tri_state"))
    )
    (net (code "204") (name "LED26") (class "Default")
      (node (ref "RN7") (pin "6") (pinfunction "2_6") (pintype "passive"))
      (node (ref "U5") (pin "2") (pinfunction "QC_2") (pintype "tri_state"))
    )
    (net (code "205") (name "LED27") (class "Default")
      (node (ref "RN7") (pin "5") (pinfunction "2_5") (pintype "passive"))
      (node (ref "U5") (pin "3") (pinfunction "QD_3") (pintype "tri_state"))
    )
    (net (code "206") (name "LED28") (class "Default")
      (node (ref "RN8") (pin "8") (pinfunction "2_8") (pintype "passive"))
      (node (ref "U5") (pin "4") (pinfunction "QE_4") (pintype "tri_state"))
    )
    (net (code "207") (name "LED29") (class "Default")
      (node (ref "RN8") (pin "7") (pinfunction "2_7") (pintype "passive"))
      (node (ref "U5") (pin "5") (pinfunction "QF_5") (pintype "tri_state"))
    )
    (net (code "208") (name "LED30") (class "Default")
      (node (ref "RN8") (pin "6") (pinfunction "2_6") (pintype "passive"))
      (node (ref "U5") (pin "6") (pinfunction "QG_6") (pintype "tri_state"))
    )
    (net (code "209") (name "LED31") (class "Default")
      (node (ref "RN8") (pin "5") (pinfunction "2_5") (pintype "passive"))
      (node (ref "U5") (pin "7") (pinfunction "QH_7") (pintype "tri_state"))
    )
    (net (code "210") (name "LED32") (class "Default")
      (node (ref "RN9") (pin "8") (pinfunction "2_8") (pintype "passive"))
      (node (ref "U6") (pin "15") (pinfunction "QA_15") (pintype "tri_state"))
    )
    (net (code "211") (name "LED33") (class "Default")
      (node (ref "RN9") (pin "7") (pinfunction "2_7") (pintype "passive"))
      (node (ref "U6") (pin "1") (pinfunction "QB_1") (pintype "tri_state"))
    )
    (net (code "212") (name "LED34") (class "Default")
      (node (ref "RN9") (pin "6") (pinfunction "2_6") (pintype "passive"))
      (node (ref "U6") (pin "2") (pinfunction "QC_2") (pintype "tri_state"))
    )
    (net (code "213") (name "LED35") (class "Default")
      (node (ref "RN9") (pin "5") (pinfunction "2_5") (pintype "passive"))
      (node (ref "U6") (pin "3") (pinfunction "QD_3") (pintype "tri_state"))
    )
    (net (code "214") (name "LED36") (class "Default")
      (node (ref "RN10") (pin "8") (pinfunction "2_8") (pintype "passive"))
      (node (ref "U6") (pin "4") (pinfunction "QE_4") (pintype "tri_state"))
    )
    (net (code "215") (name "LED37") (class "Default")
      (node (ref "RN10") (pin "7") (pinfunction "2_7") (pintype "passive"))
      (node (ref "U6") (pin "5") (pinfunction "QF_5") (pintype "tri_state"))
    )
    (net (code "216") (name "LED38") (class "Default")
      (node (ref "RN10") (pin "6") (pinfunction "2_6") (pintype "passive"))
      (node (ref "U6") (pin "6") (pinfunction "QG_6") (pintype "tri_state"))
    )
    (net (code "217") (name "LED39") (class "Default")
      (node (ref "RN10") (pin "5") (pinfunction "2_5") (pintype "passive"))
      (node (ref "U6") (pin "7") (pinfunction "QH_7") (pintype "tri_state"))
    )
    (net (code "218") (name "LED40") (class "Default")
      (node (ref "RN11") (pin "8") (pinfunction "2_8") (pintype "passive"))
      (node (ref "U7") (pin "15") (pinfunction "QA_15") (pintype "tri_state"))
    )
    (net (code "219") (name "LED41") (class "Default")
      (node (ref "RN11") (pin "7") (pinfunction "2_7") (pintype "passive"))
      (node (ref "U7") (pin "1") (pinfunction "QB_1") (pintype "tri_state"))
    )
    (net (code "220") (name "LED42") (class "Default")
      (node (ref "RN11") (pin "6") (pinfunction "2_6") (pintype "passive"))
      (node (ref "U7") (pin "2") (pinfunction "QC_2") (pintype "tri_state"))
    )
    (net (code "221") (name "LED43") (class "Default")
      (node (ref "RN11") (pin "5") (pinfunction "2_5") (pintype "passive"))
      (node (ref "U7") (pin "3") (pinfunction "QD_3") (pintype "tri_state"))
    )
    (net (code "222") (name "LED44") (class "Default")
      (node (ref "RN12") (pin "8") (pinfunction "2_8") (pintype "passive"))
      (node (ref "U7") (pin "4") (pinfunction "QE_4") (pintype "tri_state"))
    )
    (net (code "223") (name "LED45") (class "Default")
      (node (ref "RN12") (pin "7") (pinfunction "2_7") (pintype "passive"))
      (node (ref "U7") (pin "5") (pinfunction "QF_5") (pintype "tri_state"))
    )
    (net (code "224") (name "LED46") (class "Default")
      (node (ref "RN12") (pin "6") (pinfunction "2_6") (pintype "passive"))
      (node (ref "U7") (pin "6") (pinfunction "QG_6") (pintype "tri_state"))
    )
    (net (code "225") (name "LED47") (class "Default")
      (node (ref "RN12") (pin "5") (pinfunction "2_5") (pintype "passive"))
      (node (ref "U7") (pin "7") (pinfunction "QH_7") (pintype "tri_state"))
    )
    (net (code "226") (name "LED48") (class "Default")
      (node (ref "RN13") (pin "8") (pinfunction "2_8") (pintype "passive"))
      (node (ref "U8") (pin "15") (pinfunction "QA_15") (pintype "tri_state"))
    )
    (net (code "227") (name "LED49") (class "Default")
      (node (ref "RN13") (pin "7") (pinfunction "2_7") (pintype "passive"))
      (node (ref "U8") (pin "1") (pinfunction "QB_1") (pintype "tri_state"))
    )
    (net (code "228") (name "LED50") (class "Default")
      (node (ref "RN13") (pin "6") (pinfunction "2_6") (pintype "passive"))
      (node (ref "U8") (pin "2") (pinfunction "QC_2") (pintype "tri_state"))
    )
    (net (code "229") (name "LED51") (class "Default")
      (node (ref "RN13") (pin "5") (pinfunction "2_5") (pintype "passive"))
      (node (ref "U8") (pin "3") (pinfunction "QD_3") (pintype "tri_state"))
    )
    (net (code "230") (name "LED52") (class "Default")
      (node (ref "RN14") (pin "8") (pinfunction "2_8") (pintype "passive"))
      (node (ref "U8") (pin "4") (pinfunction "QE_4") (pintype "tri_state"))
    )
    (net (code "231") (name "LED53") (class "Default")
      (node (ref "RN14") (pin "7") (pinfunction "2_7") (pintype "passive"))
      (node (ref "U8") (pin "5") (pinfunction "QF_5") (pintype "tri_state"))
    )
    (net (code "232") (name "LED54") (class "Default")
      (node (ref "RN14") (pin "6") (pinfunction "2_6") (pintype "passive"))
      (node (ref "U8") (pin "6") (pinfunction "QG_6") (pintype "tri_state"))
    )
    (net (code "233") (name "LED55") (class "Default")
      (node (ref "RN14") (pin "5") (pinfunction "2_5") (pintype "passive"))
      (node (ref "U8") (pin "7") (pinfunction "QH_7") (pintype "tri_state"))
    )
    (net (code "234") (name "LED56") (class "Default")
      (node (ref "RN15") (pin "8") (pinfunction "2_8") (pintype "passive"))
      (node (ref "U9") (pin "15") (pinfunction "QA_15") (pintype "tri_state"))
    )
    (net (code "235") (name "LED57") (class "Default")
      (node (ref "RN15") (pin "7") (pinfunction "2_7") (pintype "passive"))
      (node (ref "U9") (pin "1") (pinfunction "QB_1") (pintype "tri_state"))
    )
    (net (code "236") (name "LED58") (class "Default")
      (node (ref "RN15") (pin "6") (pinfunction "2_6") (pintype "passive"))
      (node (ref "U9") (pin "2") (pinfunction "QC_2") (pintype "tri_state"))
    )
    (net (code "237") (name "LED59") (class "Default")
      (node (ref "RN15") (pin "5") (pinfunction "2_5") (pintype "passive"))
      (node (ref "U9") (pin "3") (pinfunction "QD_3") (pintype "tri_state"))
    )
    (net (code "238") (name "LED60") (class "Default")
      (node (ref "RN16") (pin "8") (pinfunction "2_8") (pintype "passive"))
      (node (ref "U9") (pin "4") (pinfunction "QE_4") (pintype "tri_state"))
    )
    (net (code "239") (name "LED61") (class "Default")
      (node (ref "RN16") (pin "7") (pinfunction "2_7") (pintype "passive"))
      (node (ref "U9") (pin "5") (pinfunction "QF_5") (pintype "tri_state"))
    )
    (net (code "240") (name "LED62") (class "Default")
      (node (ref "RN16") (pin "6") (pinfunction "2_6") (pintype "passive"))
      (node (ref "U9") (pin "6") (pinfunction "QG_6") (pintype "tri_state"))
    )
    (net (code "241") (name "LED63") (class "Default")
      (node (ref "RN16") (pin "5") (pinfunction "2_5") (pintype "passive"))
      (node (ref "U9") (pin "7") (pinfunction "QH_7") (pintype "tri_state"))
    )
    (net (code "242") (name "LED64") (class "Default")
      (node (ref "RN17") (pin "8") (pinfunction "2_8") (pintype "passive"))
      (node (ref "U10") (pin "15") (pinfunction "QA_15") (pintype "tri_state"))
    )
    (net (code "243") (name "LED65") (class "Default")
      (node (ref "RN17") (pin "7") (pinfunction "2_7") (pintype "passive"))
      (node (ref "U10") (pin "1") (pinfunction "QB_1") (pintype "tri_state"))
    )
    (net (code "244") (name "LED66") (class "Default")
      (node (ref "RN17") (pin "6") (pinfunction "2_6") (pintype "passive"))
      (node (ref "U10") (pin "2") (pinfunction "QC_2") (pintype "tri_state"))
    )
    (net (code "245") (name "LED67") (class "Default")
      (node (ref "RN17") (pin "5") (pinfunction "2_5") (pintype "passive"))
      (node (ref "U10") (pin "3") (pinfunction "QD_3") (pintype "tri_state"))
    )
    (net (code "246") (name "LED68") (class "Default")
      (node (ref "RN18") (pin "8") (pinfunction "2_8") (pintype "passive"))
      (node (ref "U10") (pin "4") (pinfunction "QE_4") (pintype "tri_state"))
    )
    (net (code "247") (name "LED69") (class "Default")
      (node (ref "RN18") (pin "7") (pinfunction "2_7") (pintype "passive"))
      (node (ref "U10") (pin "5") (pinfunction "QF_5") (pintype "tri_state"))
    )
    (net (code "248") (name "LED70") (class "Default")
      (node (ref "RN18") (pin "6") (pinfunction "2_6") (pintype "passive"))
      (node (ref "U10") (pin "6") (pinfunction "QG_6") (pintype "tri_state"))
    )
    (net (code "249") (name "LED71") (class "Default")
      (node (ref "RN18") (pin "5") (pinfunction "2_5") (pintype "passive"))
      (node (ref "U10") (pin "7") (pinfunction "QH_7") (pintype "tri_state"))
    )
    (net (code "250") (name "LED72") (class "Default")
      (node (ref "RN19") (pin "8") (pinfunction "2_8") (pintype "passive"))
      (node (ref "U11") (pin "15") (pinfunction "QA_15") (pintype "tri_state"))
    )
    (net (code "251") (name "LED73") (class "Default")
      (node (ref "RN19") (pin "7") (pinfunction "2_7") (pintype "passive"))
      (node (ref "U11") (pin "1") (pinfunction "QB_1") (pintype "tri_state"))
    )
    (net (code "252") (name "LED74") (class "Default")
      (node (ref "RN19") (pin "6") (pinfunction "2_6") (pintype "passive"))
      (node (ref "U11") (pin "2") (pinfunction "QC_2") (pintype "tri_state"))
    )
    (net (code "253") (name "LED75") (class "Default")
      (node (ref "RN19") (pin "5") (pinfunction "2_5") (pintype "passive"))
      (node (ref "U11") (pin "3") (pinfunction "QD_3") (pintype "tri_state"))
    )
    (net (code "254") (name "LED76") (class "Default")
      (node (ref "RN20") (pin "8") (pinfunction "2_8") (pintype "passive"))
      (node (ref "U11") (pin "4") (pinfunction "QE_4") (pintype "tri_state"))
    )
    (net (code "255") (name "LED77") (class "Default")
      (node (ref "RN20") (pin "7") (pinfunction "2_7") (pintype "passive"))
      (node (ref "U11") (pin "5") (pinfunction "QF_5") (pintype "tri_state"))
    )
    (net (code "256") (name "LED78") (class "Default")
      (node (ref "RN20") (pin "6") (pinfunction "2_6") (pintype "passive"))
      (node (ref "U11") (pin "6") (pinfunction "QG_6") (pintype "tri_state"))
    )
    (net (code "257") (name "LED79") (class "Default")
      (node (ref "RN20") (pin "5") (pinfunction "2_5") (pintype "passive"))
      (node (ref "U11") (pin "7") (pinfunction "QH_7") (pintype "tri_state"))
    )
    (net (code "258") (name "MISO") (class "Default")
      (node (ref "ISP1") (pin "1") (pinfunction "MISO_1") (pintype "input"))
      (node (ref "U1") (pin "16") (pinfunction "PB4(MISO)_16") (pintype "bidirectional"))
    )
    (net (code "259") (name "MOSI") (class "Default")
      (node (ref "ISP1") (pin "4") (pinfunction "MOSI_4") (pintype "output"))
      (node (ref "U1") (pin "15") (pinfunction "PB3(MOSI/OC2)_15") (pintype "bidirectional"))
    )
    (net (code "260") (name "Net-(C6-Pad1)") (class "Default")
      (node (ref "C6") (pin "1") (pinfunction "1_1") (pintype "passive"))
      (node (ref "R7") (pin "2") (pinfunction "2_2") (pintype "passive"))
      (node (ref "R8") (pin "1") (pinfunction "1_1") (pintype "passive"))
    )
    (net (code "261") (name "Net-(D1-A)") (class "Default")
      (node (ref "D1") (pin "2") (pinfunction "A_2") (pintype "passive"))
      (node (ref "R3") (pin "2") (pinfunction "2_2") (pintype "passive"))
      (node (ref "R4") (pin "1") (pinfunction "1_1") (pintype "passive"))
    )
    (net (code "262") (name "Net-(D1-C)") (class "Default")
      (node (ref "D1") (pin "1") (pinfunction "C_1") (pintype "passive"))
      (node (ref "D2") (pin "2") (pinfunction "A_2") (pintype "passive"))
      (node (ref "IC1") (pin "1") (pinfunction "OUT_1") (pintype "output"))
    )
    (net (code "263") (name "Net-(D2-C)") (class "Default")
      (node (ref "D2") (pin "1") (pinfunction "C_1") (pintype "passive"))
      (node (ref "IC1") (pin "5") (pinfunction "+IN_5") (pintype "input"))
      (node (ref "R9") (pin "2") (pinfunction "2_2") (pintype "passive"))
    )
    (net (code "264") (name "Net-(D3-A)") (class "Default")
      (node (ref "D3") (pin "P$10") (pinfunction "A_P$10") (pintype "passive"))
      (node (ref "RN3") (pin "2") (pinfunction "1_2") (pintype "passive"))
    )
    (net (code "265") (name "Net-(D3-A1)") (class "Default")
      (node (ref "D3") (pin "P$9") (pinfunction "A1_P$9") (pintype "passive"))
      (node (ref "RN3") (pin "1") (pinfunction "1_1") (pintype "passive"))
    )
    (net (code "266") (name "Net-(D3-A2)") (class "Default")
      (node (ref "D3") (pin "P$8") (pinfunction "A2_P$8") (pintype "passive"))
      (node (ref "RN2") (pin "4") (pinfunction "1_4") (pintype "passive"))
    )
    (net (code "267") (name "Net-(D3-A3)") (class "Default")
      (node (ref "D3") (pin "P$7") (pinfunction "A3_P$7") (pintype "passive"))
      (node (ref "RN2") (pin "3") (pinfunction "1_3") (pintype "passive"))
    )
    (net (code "268") (name "Net-(D3-A4)") (class "Default")
      (node (ref "D3") (pin "P$6") (pinfunction "A4_P$6") (pintype "passive"))
      (node (ref "RN2") (pin "2") (pinfunction "1_2") (pintype "passive"))
    )
    (net (code "269") (name "Net-(D3-A5)") (class "Default")
      (node (ref "D3") (pin "P$5") (pinfunction "A5_P$5") (pintype "passive"))
      (node (ref "RN2") (pin "1") (pinfunction "1_1") (pintype "passive"))
    )
    (net (code "270") (name "Net-(D3-A6)") (class "Default")
      (node (ref "D3") (pin "P$4") (pinfunction "A6_P$4") (pintype "passive"))
      (node (ref "RN1") (pin "4") (pinfunction "1_4") (pintype "passive"))
    )
    (net (code "271") (name "Net-(D3-A7)") (class "Default")
      (node (ref "D3") (pin "P$3") (pinfunction "A7_P$3") (pintype "passive"))
      (node (ref "RN1") (pin "3") (pinfunction "1_3") (pintype "passive"))
    )
    (net (code "272") (name "Net-(D3-A8)") (class "Default")
      (node (ref "D3") (pin "P$2") (pinfunction "A8_P$2") (pintype "passive"))
      (node (ref "RN1") (pin "2") (pinfunction "1_2") (pintype "passive"))
    )
    (net (code "273") (name "Net-(D3-A9)") (class "Default")
      (node (ref "D3") (pin "P$1") (pinfunction "A9_P$1") (pintype "passive"))
      (node (ref "RN1") (pin "1") (pinfunction "1_1") (pintype "passive"))
    )
    (net (code "274") (name "Net-(D4-A)") (class "Default")
      (node (ref "D4") (pin "P$10") (pinfunction "A_P$10") (pintype "passive"))
      (node (ref "RN5") (pin "4") (pinfunction "1_4") (pintype "passive"))
    )
    (net (code "275") (name "Net-(D4-A1)") (class "Default")
      (node (ref "D4") (pin "P$9") (pinfunction "A1_P$9") (pintype "passive"))
      (node (ref "RN5") (pin "3") (pinfunction "1_3") (pintype "passive"))
    )
    (net (code "276") (name "Net-(D4-A2)") (class "Default")
      (node (ref "D4") (pin "P$8") (pinfunction "A2_P$8") (pintype "passive"))
      (node (ref "RN5") (pin "2") (pinfunction "1_2") (pintype "passive"))
    )
    (net (code "277") (name "Net-(D4-A3)") (class "Default")
      (node (ref "D4") (pin "P$7") (pinfunction "A3_P$7") (pintype "passive"))
      (node (ref "RN5") (pin "1") (pinfunction "1_1") (pintype "passive"))
    )
    (net (code "278") (name "Net-(D4-A4)") (class "Default")
      (node (ref "D4") (pin "P$6") (pinfunction "A4_P$6") (pintype "passive"))
      (node (ref "RN4") (pin "4") (pinfunction "1_4") (pintype "passive"))
    )
    (net (code "279") (name "Net-(D4-A5)") (class "Default")
      (node (ref "D4") (pin "P$5") (pinfunction "A5_P$5") (pintype "passive"))
      (node (ref "RN4") (pin "3") (pinfunction "1_3") (pintype "passive"))
    )
    (net (code "280") (name "Net-(D4-A6)") (class "Default")
      (node (ref "D4") (pin "P$4") (pinfunction "A6_P$4") (pintype "passive"))
      (node (ref "RN4") (pin "2") (pinfunction "1_2") (pintype "passive"))
    )
    (net (code "281") (name "Net-(D4-A7)") (class "Default")
      (node (ref "D4") (pin "P$3") (pinfunction "A7_P$3") (pintype "passive"))
      (node (ref "RN4") (pin "1") (pinfunction "1_1") (pintype "passive"))
    )
    (net (code "282") (name "Net-(D4-A8)") (class "Default")
      (node (ref "D4") (pin "P$2") (pinfunction "A8_P$2") (pintype "passive"))
      (node (ref "RN3") (pin "4") (pinfunction "1_4") (pintype "passive"))
    )
    (net (code "283") (name "Net-(D4-A9)") (class "Default")
      (node (ref "D4") (pin "P$1") (pinfunction "A9_P$1") (pintype "passive"))
      (node (ref "RN3") (pin "3") (pinfunction "1_3") (pintype "passive"))
    )
    (net (code "284") (name "Net-(D5-A)") (class "Default")
      (node (ref "D5") (pin "P$10") (pinfunction "A_P$10") (pintype "passive"))
      (node (ref "RN8") (pin "2") (pinfunction "1_2") (pintype "passive"))
    )
    (net (code "285") (name "Net-(D5-A1)") (class "Default")
      (node (ref "D5") (pin "P$9") (pinfunction "A1_P$9") (pintype "passive"))
      (node (ref "RN8") (pin "1") (pinfunction "1_1") (pintype "passive"))
    )
    (net (code "286") (name "Net-(D5-A2)") (class "Default")
      (node (ref "D5") (pin "P$8") (pinfunction "A2_P$8") (pintype "passive"))
      (node (ref "RN7") (pin "4") (pinfunction "1_4") (pintype "passive"))
    )
    (net (code "287") (name "Net-(D5-A3)") (class "Default")
      (node (ref "D5") (pin "P$7") (pinfunction "A3_P$7") (pintype "passive"))
      (node (ref "RN7") (pin "3") (pinfunction "1_3") (pintype "passive"))
    )
    (net (code "288") (name "Net-(D5-A4)") (class "Default")
      (node (ref "D5") (pin "P$6") (pinfunction "A4_P$6") (pintype "passive"))
      (node (ref "RN7") (pin "2") (pinfunction "1_2") (pintype "passive"))
    )
    (net (code "289") (name "Net-(D5-A5)") (class "Default")
      (node (ref "D5") (pin "P$5") (pinfunction "A5_P$5") (pintype "passive"))
      (node (ref "RN7") (pin "1") (pinfunction "1_1") (pintype "passive"))
    )
    (net (code "290") (name "Net-(D5-A6)") (class "Default")
      (node (ref "D5") (pin "P$4") (pinfunction "A6_P$4") (pintype "passive"))
      (node (ref "RN6") (pin "4") (pinfunction "1_4") (pintype "passive"))
    )
    (net (code "291") (name "Net-(D5-A7)") (class "Default")
      (node (ref "D5") (pin "P$3") (pinfunction "A7_P$3") (pintype "passive"))
      (node (ref "RN6") (pin "3") (pinfunction "1_3") (pintype "passive"))
    )
    (net (code "292") (name "Net-(D5-A8)") (class "Default")
      (node (ref "D5") (pin "P$2") (pinfunction "A8_P$2") (pintype "passive"))
      (node (ref "RN6") (pin "2") (pinfunction "1_2") (pintype "passive"))
    )
    (net (code "293") (name "Net-(D5-A9)") (class "Default")
      (node (ref "D5") (pin "P$1") (pinfunction "A9_P$1") (pintype "passive"))
      (node (ref "RN6") (pin "1") (pinfunction "1_1") (pintype "passive"))
    )
    (net (code "294") (name "Net-(D6-A)") (class "Default")
      (node (ref "D6") (pin "P$10") (pinfunction "A_P$10") (pintype "passive"))
      (node (ref "RN10") (pin "4") (pinfunction "1_4") (pintype "passive"))
    )
    (net (code "295") (name "Net-(D6-A1)") (class "Default")
      (node (ref "D6") (pin "P$9") (pinfunction "A1_P$9") (pintype "passive"))
      (node (ref "RN10") (pin "3") (pinfunction "1_3") (pintype "passive"))
    )
    (net (code "296") (name "Net-(D6-A2)") (class "Default")
      (node (ref "D6") (pin "P$8") (pinfunction "A2_P$8") (pintype "passive"))
      (node (ref "RN10") (pin "2") (pinfunction "1_2") (pintype "passive"))
    )
    (net (code "297") (name "Net-(D6-A3)") (class "Default")
      (node (ref "D6") (pin "P$7") (pinfunction "A3_P$7") (pintype "passive"))
      (node (ref "RN10") (pin "1") (pinfunction "1_1") (pintype "passive"))
    )
    (net (code "298") (name "Net-(D6-A4)") (class "Default")
      (node (ref "D6") (pin "P$6") (pinfunction "A4_P$6") (pintype "passive"))
      (node (ref "RN9") (pin "4") (pinfunction "1_4") (pintype "passive"))
    )
    (net (code "299") (name "Net-(D6-A5)") (class "Default")
      (node (ref "D6") (pin "P$5") (pinfunction "A5_P$5") (pintype "passive"))
      (node (ref "RN9") (pin "3") (pinfunction "1_3") (pintype "passive"))
    )
    (net (code "300") (name "Net-(D6-A6)") (class "Default")
      (node (ref "D6") (pin "P$4") (pinfunction "A6_P$4") (pintype "passive"))
      (node (ref "RN9") (pin "2") (pinfunction "1_2") (pintype "passive"))
    )
    (net (code "301") (name "Net-(D6-A7)") (class "Default")
      (node (ref "D6") (pin "P$3") (pinfunction "A7_P$3") (pintype "passive"))
      (node (ref "RN9") (pin "1") (pinfunction "1_1") (pintype "passive"))
    )
    (net (code "302") (name "Net-(D6-A8)") (class "Default")
      (node (ref "D6") (pin "P$2") (pinfunction "A8_P$2") (pintype "passive"))
      (node (ref "RN8") (pin "4") (pinfunction "1_4") (pintype "passive"))
    )
    (net (code "303") (name "Net-(D6-A9)") (class "Default")
      (node (ref "D6") (pin "P$1") (pinfunction "A9_P$1") (pintype "passive"))
      (node (ref "RN8") (pin "3") (pinfunction "1_3") (pintype "passive"))
    )
    (net (code "304") (name "Net-(D7-A)") (class "Default")
      (node (ref "D7") (pin "P$10") (pinfunction "A_P$10") (pintype "passive"))
      (node (ref "RN13") (pin "2") (pinfunction "1_2") (pintype "passive"))
    )
    (net (code "305") (name "Net-(D7-A1)") (class "Default")
      (node (ref "D7") (pin "P$9") (pinfunction "A1_P$9") (pintype "passive"))
      (node (ref "RN13") (pin "1") (pinfunction "1_1") (pintype "passive"))
    )
    (net (code "306") (name "Net-(D7-A2)") (class "Default")
      (node (ref "D7") (pin "P$8") (pinfunction "A2_P$8") (pintype "passive"))
      (node (ref "RN12") (pin "4") (pinfunction "1_4") (pintype "passive"))
    )
    (net (code "307") (name "Net-(D7-A3)") (class "Default")
      (node (ref "D7") (pin "P$7") (pinfunction "A3_P$7") (pintype "passive"))
      (node (ref "RN12") (pin "3") (pinfunction "1_3") (pintype "passive"))
    )
    (net (code "308") (name "Net-(D7-A4)") (class "Default")
      (node (ref "D7") (pin "P$6") (pinfunction "A4_P$6") (pintype "passive"))
      (node (ref "RN12") (pin "2") (pinfunction "1_2") (pintype "passive"))
    )
    (net (code "309") (name "Net-(D7-A5)") (class "Default")
      (node (ref "D7") (pin "P$5") (pinfunction "A5_P$5") (pintype "passive"))
      (node (ref "RN12") (pin "1") (pinfunction "1_1") (pintype "passive"))
    )
    (net (code "310") (name "Net-(D7-A6)") (class "Default")
      (node (ref "D7") (pin "P$4") (pinfunction "A6_P$4") (pintype "passive"))
      (node (ref "RN11") (pin "4") (pinfunction "1_4") (pintype "passive"))
    )
    (net (code "311") (name "Net-(D7-A7)") (class "Default")
      (node (ref "D7") (pin "P$3") (pinfunction "A7_P$3") (pintype "passive"))
      (node (ref "RN11") (pin "3") (pinfunction "1_3") (pintype "passive"))
    )
    (net (code "312") (name "Net-(D7-A8)") (class "Default")
      (node (ref "D7") (pin "P$2") (pinfunction "A8_P$2") (pintype "passive"))
      (node (ref "RN11") (pin "2") (pinfunction "1_2") (pintype "passive"))
    )
    (net (code "313") (name "Net-(D7-A9)") (class "Default")
      (node (ref "D7") (pin "P$1") (pinfunction "A9_P$1") (pintype "passive"))
      (node (ref "RN11") (pin "1") (pinfunction "1_1") (pintype "passive"))
    )
    (net (code "314") (name "Net-(D8-A)") (class "Default")
      (node (ref "D8") (pin "P$10") (pinfunction "A_P$10") (pintype "passive"))
      (node (ref "RN15") (pin "4") (pinfunction "1_4") (pintype "passive"))
    )
    (net (code "315") (name "Net-(D8-A1)") (class "Default")
      (node (ref "D8") (pin "P$9") (pinfunction "A1_P$9") (pintype "passive"))
      (node (ref "RN15") (pin "3") (pinfunction "1_3") (pintype "passive"))
    )
    (net (code "316") (name "Net-(D8-A2)") (class "Default")
      (node (ref "D8") (pin "P$8") (pinfunction "A2_P$8") (pintype "passive"))
      (node (ref "RN15") (pin "2") (pinfunction "1_2") (pintype "passive"))
    )
    (net (code "317") (name "Net-(D8-A3)") (class "Default")
      (node (ref "D8") (pin "P$7") (pinfunction "A3_P$7") (pintype "passive"))
      (node (ref "RN15") (pin "1") (pinfunction "1_1") (pintype "passive"))
    )
    (net (code "318") (name "Net-(D8-A4)") (class "Default")
      (node (ref "D8") (pin "P$6") (pinfunction "A4_P$6") (pintype "passive"))
      (node (ref "RN14") (pin "4") (pinfunction "1_4") (pintype "passive"))
    )
    (net (code "319") (name "Net-(D8-A5)") (class "Default")
      (node (ref "D8") (pin "P$5") (pinfunction "A5_P$5") (pintype "passive"))
      (node (ref "RN14") (pin "3") (pinfunction "1_3") (pintype "passive"))
    )
    (net (code "320") (name "Net-(D8-A6)") (class "Default")
      (node (ref "D8") (pin "P$4") (pinfunction "A6_P$4") (pintype "passive"))
      (node (ref "RN14") (pin "2") (pinfunction "1_2") (pintype "passive"))
    )
    (net (code "321") (name "Net-(D8-A7)") (class "Default")
      (node (ref "D8") (pin "P$3") (pinfunction "A7_P$3") (pintype "passive"))
      (node (ref "RN14") (pin "1") (pinfunction "1_1") (pintype "passive"))
    )
    (net (code "322") (name "Net-(D8-A8)") (class "Default")
      (node (ref "D8") (pin "P$2") (pinfunction "A8_P$2") (pintype "passive"))
      (node (ref "RN13") (pin "4") (pinfunction "1_4") (pintype "passive"))
    )
    (net (code "323") (name "Net-(D8-A9)") (class "Default")
      (node (ref "D8") (pin "P$1") (pinfunction "A9_P$1") (pintype "passive"))
      (node (ref "RN13") (pin "3") (pinfunction "1_3") (pintype "passive"))
    )
    (net (code "324") (name "Net-(D9-A)") (class "Default")
      (node (ref "D9") (pin "P$10") (pinfunction "A_P$10") (pintype "passive"))
      (node (ref "RN18") (pin "2") (pinfunction "1_2") (pintype "passive"))
    )
    (net (code "325") (name "Net-(D9-A1)") (class "Default")
      (node (ref "D9") (pin "P$9") (pinfunction "A1_P$9") (pintype "passive"))
      (node (ref "RN18") (pin "1") (pinfunction "1_1") (pintype "passive"))
    )
    (net (code "326") (name "Net-(D9-A2)") (class "Default")
      (node (ref "D9") (pin "P$8") (pinfunction "A2_P$8") (pintype "passive"))
      (node (ref "RN17") (pin "4") (pinfunction "1_4") (pintype "passive"))
    )
    (net (code "327") (name "Net-(D9-A3)") (class "Default")
      (node (ref "D9") (pin "P$7") (pinfunction "A3_P$7") (pintype "passive"))
      (node (ref "RN17") (pin "3") (pinfunction "1_3") (pintype "passive"))
    )
    (net (code "328") (name "Net-(D9-A4)") (class "Default")
      (node (ref "D9") (pin "P$6") (pinfunction "A4_P$6") (pintype "passive"))
      (node (ref "RN17") (pin "2") (pinfunction "1_2") (pintype "passive"))
    )
    (net (code "329") (name "Net-(D9-A5)") (class "Default")
      (node (ref "D9") (pin "P$5") (pinfunction "A5_P$5") (pintype "passive"))
      (node (ref "RN17") (pin "1") (pinfunction "1_1") (pintype "passive"))
    )
    (net (code "330") (name "Net-(D9-A6)") (class "Default")
      (node (ref "D9") (pin "P$4") (pinfunction "A6_P$4") (pintype "passive"))
      (node (ref "RN16") (pin "4") (pinfunction "1_4") (pintype "passive"))
    )
    (net (code "331") (name "Net-(D9-A7)") (class "Default")
      (node (ref "D9") (pin "P$3") (pinfunction "A7_P$3") (pintype "passive"))
      (node (ref "RN16") (pin "3") (pinfunction "1_3") (pintype "passive"))
    )
    (net (code "332") (name "Net-(D9-A8)") (class "Default")
      (node (ref "D9") (pin "P$2") (pinfunction "A8_P$2") (pintype "passive"))
      (node (ref "RN16") (pin "2") (pinfunction "1_2") (pintype "passive"))
    )
    (net (code "333") (name "Net-(D9-A9)") (class "Default")
      (node (ref "D9") (pin "P$1") (pinfunction "A9_P$1") (pintype "passive"))
      (node (ref "RN16") (pin "1") (pinfunction "1_1") (pintype "passive"))
    )
    (net (code "334") (name "Net-(D10-A)") (class "Default")
      (node (ref "D10") (pin "P$10") (pinfunction "A_P$10") (pintype "passive"))
      (node (ref "RN20") (pin "4") (pinfunction "1_4") (pintype "passive"))
    )
    (net (code "335") (name "Net-(D10-A1)") (class "Default")
      (node (ref "D10") (pin "P$9") (pinfunction "A1_P$9") (pintype "passive"))
      (node (ref "RN20") (pin "3") (pinfunction "1_3") (pintype "passive"))
    )
    (net (code "336") (name "Net-(D10-A2)") (class "Default")
      (node (ref "D10") (pin "P$8") (pinfunction "A2_P$8") (pintype "passive"))
      (node (ref "RN20") (pin "2") (pinfunction "1_2") (pintype "passive"))
    )
    (net (code "337") (name "Net-(D10-A3)") (class "Default")
      (node (ref "D10") (pin "P$7") (pinfunction "A3_P$7") (pintype "passive"))
      (node (ref "RN20") (pin "1") (pinfunction "1_1") (pintype "passive"))
    )
    (net (code "338") (name "Net-(D10-A4)") (class "Default")
      (node (ref "D10") (pin "P$6") (pinfunction "A4_P$6") (pintype "passive"))
      (node (ref "RN19") (pin "4") (pinfunction "1_4") (pintype "passive"))
    )
    (net (code "339") (name "Net-(D10-A5)") (class "Default")
      (node (ref "D10") (pin "P$5") (pinfunction "A5_P$5") (pintype "passive"))
      (node (ref "RN19") (pin "3") (pinfunction "1_3") (pintype "passive"))
    )
    (net (code "340") (name "Net-(D10-A6)") (class "Default")
      (node (ref "D10") (pin "P$4") (pinfunction "A6_P$4") (pintype "passive"))
      (node (ref "RN19") (pin "2") (pinfunction "1_2") (pintype "passive"))
    )
    (net (code "341") (name "Net-(D10-A7)") (class "Default")
      (node (ref "D10") (pin "P$3") (pinfunction "A7_P$3") (pintype "passive"))
      (node (ref "RN19") (pin "1") (pinfunction "1_1") (pintype "passive"))
    )
    (net (code "342") (name "Net-(D10-A8)") (class "Default")
      (node (ref "D10") (pin "P$2") (pinfunction "A8_P$2") (pintype "passive"))
      (node (ref "RN18") (pin "4") (pinfunction "1_4") (pintype "passive"))
    )
    (net (code "343") (name "Net-(D10-A9)") (class "Default")
      (node (ref "D10") (pin "P$1") (pinfunction "A9_P$1") (pintype "passive"))
      (node (ref "RN18") (pin "3") (pinfunction "1_3") (pintype "passive"))
    )
    (net (code "344") (name "Net-(IC1A--IN)") (class "Default")
      (node (ref "IC1") (pin "2") (pinfunction "-IN_2") (pintype "input"))
      (node (ref "R3") (pin "1") (pinfunction "1_1") (pintype "passive"))
      (node (ref "R6") (pin "2") (pinfunction "2_2") (pintype "passive"))
      (node (ref "R9") (pin "1") (pinfunction "1_1") (pintype "passive"))
    )
    (net (code "345") (name "Net-(IC1B--IN)") (class "Default")
      (node (ref "IC1") (pin "6") (pinfunction "-IN_6") (pintype "input"))
      (node (ref "R4") (pin "2") (pinfunction "2_2") (pintype "passive"))
      (node (ref "R5") (pin "1") (pinfunction "1_1") (pintype "passive"))
    )
    (net (code "346") (name "Net-(IC1C-+IN)") (class "Default")
      (node (ref "C7") (pin "2") (pinfunction "2_2") (pintype "passive"))
      (node (ref "IC1") (pin "10") (pinfunction "+IN_10") (pintype "input"))
      (node (ref "R8") (pin "2") (pinfunction "2_2") (pintype "passive"))
    )
    (net (code "347") (name "Net-(IC1D-+IN)") (class "Default")
      (node (ref "IC1") (pin "12") (pinfunction "+IN_12") (pintype "input"))
      (node (ref "R10") (pin "1") (pinfunction "1_1") (pintype "passive"))
      (node (ref "R11") (pin "1") (pinfunction "1_1") (pintype "passive"))
    )
    (net (code "348") (name "Net-(IC1D--IN)") (class "Default")
      (node (ref "IC1") (pin "13") (pinfunction "-IN_13") (pintype "input"))
      (node (ref "IC1") (pin "14") (pinfunction "OUT_14") (pintype "output"))
    )
    (net (code "349") (name "Net-(J2-TIP)") (class "Default")
      (node (ref "J2") (pin "1") (pinfunction "TIP_1") (pintype "bidirectional"))
      (node (ref "R6") (pin "1") (pinfunction "1_1") (pintype "passive"))
    )
    (net (code "350") (name "Net-(U1-AREF)") (class "Default")
      (node (ref "C1") (pin "2") (pinfunction "2_2") (pintype "passive"))
      (node (ref "U1") (pin "20") (pinfunction "AREF_20") (pintype "bidirectional"))
    )
    (net (code "351") (name "Net-(U1-PB0(ICP))") (class "Default")
      (node (ref "J4") (pin "4") (pinfunction "4_4") (pintype "passive"))
      (node (ref "U1") (pin "12") (pinfunction "PB0(ICP)_12") (pintype "bidirectional"))
    )
    (net (code "352") (name "Net-(U1-PB1(OC1A))") (class "Default")
      (node (ref "J4") (pin "3") (pinfunction "3_3") (pintype "passive"))
      (node (ref "U1") (pin "13") (pinfunction "PB1(OC1A)_13") (pintype "bidirectional"))
    )
    (net (code "353") (name "Net-(U1-PB2(SS{slash}OC1B))") (class "Default")
      (node (ref "J4") (pin "2") (pinfunction "2_2") (pintype "passive"))
      (node (ref "U1") (pin "14") (pinfunction "PB2(SS/OC1B)_14") (pintype "bidirectional"))
    )
    (net (code "354") (name "Net-(U1-PB6(XTAL1{slash}TOSC1))") (class "Default")
      (node (ref "C2") (pin "2") (pinfunction "2_2") (pintype "passive"))
      (node (ref "U1") (pin "7") (pinfunction "PB6(XTAL1/TOSC1)_7") (pintype "bidirectional"))
      (node (ref "Y1") (pin "3") (pinfunction "2_3") (pintype "passive"))
    )
    (net (code "355") (name "Net-(U1-PB7(XTAL2{slash}TOSC2))") (class "Default")
      (node (ref "C3") (pin "2") (pinfunction "2_2") (pintype "passive"))
      (node (ref "U1") (pin "8") (pinfunction "PB7(XTAL2/TOSC2)_8") (pintype "bidirectional"))
      (node (ref "Y1") (pin "1") (pinfunction "1_1") (pintype "passive"))
    )
    (net (code "356") (name "Net-(U1-PD0(RXD))") (class "Default")
      (node (ref "J3") (pin "2") (pinfunction "2_2") (pintype "passive"))
      (node (ref "U1") (pin "30") (pinfunction "PD0(RXD)_30") (pintype "bidirectional"))
    )
    (net (code "357") (name "Net-(U1-PD1(TXD))") (class "Default")
      (node (ref "J3") (pin "1") (pinfunction "1_1") (pintype "passive"))
      (node (ref "U1") (pin "31") (pinfunction "PD1(TXD)_31") (pintype "bidirectional"))
    )
    (net (code "358") (name "Net-(U2-QH*)") (class "Default")
      (node (ref "U2") (pin "9") (pinfunction "QH*_9") (pintype "tri_state"))
      (node (ref "U3") (pin "14") (pinfunction "SER_14") (pintype "input"))
    )
    (net (code "359") (name "Net-(U3-QH*)") (class "Default")
      (node (ref "U3") (pin "9") (pinfunction "QH*_9") (pintype "tri_state"))
      (node (ref "U4") (pin "14") (pinfunction "SER_14") (pintype "input"))
    )
    (net (code "360") (name "Net-(U4-QH*)") (class "Default")
      (node (ref "U4") (pin "9") (pinfunction "QH*_9") (pintype "tri_state"))
      (node (ref "U5") (pin "14") (pinfunction "SER_14") (pintype "input"))
    )
    (net (code "361") (name "Net-(U5-QH*)") (class "Default")
      (node (ref "U5") (pin "9") (pinfunction "QH*_9") (pintype "tri_state"))
      (node (ref "U6") (pin "14") (pinfunction "SER_14") (pintype "input"))
    )
    (net (code "362") (name "Net-(U6-QH*)") (class "Default")
      (node (ref "U6") (pin "9") (pinfunction "QH*_9") (pintype "tri_state"))
      (node (ref "U7") (pin "14") (pinfunction "SER_14") (pintype "input"))
    )
    (net (code "363") (name "Net-(U7-QH*)") (class "Default")
      (node (ref "U7") (pin "9") (pinfunction "QH*_9") (pintype "tri_state"))
      (node (ref "U8") (pin "14") (pinfunction "SER_14") (pintype "input"))
    )
    (net (code "364") (name "Net-(U8-QH*)") (class "Default")
      (node (ref "U8") (pin "9") (pinfunction "QH*_9") (pintype "tri_state"))
      (node (ref "U9") (pin "14") (pinfunction "SER_14") (pintype "input"))
    )
    (net (code "365") (name "Net-(U10-QH*)") (class "Default")
      (node (ref "U10") (pin "9") (pinfunction "QH*_9") (pintype "tri_state"))
      (node (ref "U11") (pin "14") (pinfunction "SER_14") (pintype "input"))
    )
    (net (code "366") (name "Net-(U10-SER)") (class "Default")
      (node (ref "U10") (pin "14") (pinfunction "SER_14") (pintype "input"))
      (node (ref "U9") (pin "9") (pinfunction "QH*_9") (pintype "tri_state"))
    )
    (net (code "367") (name "RCTFD_AUDIO") (class "Default")
      (node (ref "IC1") (pin "7") (pinfunction "OUT_7") (pintype "output"))
      (node (ref "R5") (pin "2") (pinfunction "2_2") (pintype "passive"))
      (node (ref "R7") (pin "1") (pinfunction "1_1") (pintype "passive"))
    )
    (net (code "368") (name "RST") (class "Default")
      (node (ref "ISP1") (pin "5") (pinfunction "RST_5") (pintype "output"))
      (node (ref "U1") (pin "29") (pinfunction "PC6(/RESET)_29") (pintype "bidirectional"))
    )
    (net (code "369") (name "THRESHOLD") (class "Default")
      (node (ref "R2") (pin "2") (pinfunction "S_2") (pintype "passive"))
      (node (ref "U1") (pin "25") (pinfunction "PC2(ADC2)_25") (pintype "bidirectional"))
    )
    (net (code "370") (name "VCC") (class "Default")
      (node (ref "C10") (pin "2") (pinfunction "2_2") (pintype "passive"))
      (node (ref "C11") (pin "2") (pinfunction "2_2") (pintype "passive"))
      (node (ref "C12") (pin "2") (pinfunction "2_2") (pintype "passive"))
      (node (ref "C13") (pin "2") (pinfunction "2_2") (pintype "passive"))
      (node (ref "C14") (pin "2") (pinfunction "2_2") (pintype "passive"))
      (node (ref "C15") (pin "2") (pinfunction "2_2") (pintype "passive"))
      (node (ref "C16") (pin "2") (pinfunction "2_2") (pintype "passive"))
      (node (ref "C17") (pin "2") (pinfunction "2_2") (pintype "passive"))
      (node (ref "C18") (pin "2") (pinfunction "2_2") (pintype "passive"))
      (node (ref "C4") (pin "1") (pinfunction "1_1") (pintype "passive"))
      (node (ref "C5") (pin "1") (pinfunction "1_1") (pintype "passive"))
      (node (ref "C8") (pin "2") (pinfunction "2_2") (pintype "passive"))
      (node (ref "C9") (pin "2") (pinfunction "2_2") (pintype "passive"))
      (node (ref "IC1") (pin "4") (pinfunction "V+_4") (pintype "power_in"))
      (node (ref "ISP1") (pin "2") (pinfunction "VCC_2") (pintype "power_in"))
      (node (ref "J1") (pin "2") (pinfunction "2_2") (pintype "passive"))
      (node (ref "R1") (pin "1") (pinfunction "E_1") (pintype "passive"))
      (node (ref "R10") (pin "2") (pinfunction "2_2") (pintype "passive"))
      (node (ref "R2") (pin "1") (pinfunction "E_1") (pintype "passive"))
      (node (ref "U1") (pin "18") (pinfunction "AVCC_18") (pintype "bidirectional"))
      (node (ref "U1") (pin "4") (pinfunction "VCC_4") (pintype "bidirectional"))
      (node (ref "U1") (pin "6") (pinfunction "VCC_6") (pintype "bidirectional"))
      (node (ref "U10") (pin "16") (pinfunction "VCC_16") (pintype "power_in"))
      (node (ref "U11") (pin "16") (pinfunction "VCC_16") (pintype "power_in"))
      (node (ref "U2") (pin "16") (pinfunction "VCC_16") (pintype "power_in"))
      (node (ref "U3") (pin "16") (pinfunction "VCC_16") (pintype "power_in"))
      (node (ref "U4") (pin "16") (pinfunction "VCC_16") (pintype "power_in"))
      (node (ref "U5") (pin "16") (pinfunction "VCC_16") (pintype "power_in"))
      (node (ref "U6") (pin "16") (pinfunction "VCC_16") (pintype "power_in"))
      (node (ref "U7") (pin "16") (pinfunction "VCC_16") (pintype "power_in"))
      (node (ref "U8") (pin "16") (pinfunction "VCC_16") (pintype "power_in"))
      (node (ref "U9") (pin "16") (pinfunction "VCC_16") (pintype "power_in"))
    )
    (net (code "371") (name "unconnected-(U1-ADC6-Pad19)") (class "Default")
      (node (ref "U1") (pin "19") (pinfunction "ADC6_19") (pintype "bidirectional"))
    )
    (net (code "372") (name "unconnected-(U1-ADC7-Pad22)") (class "Default")
      (node (ref "U1") (pin "22") (pinfunction "ADC7_22") (pintype "bidirectional"))
    )
    (net (code "373") (name "unconnected-(U1-PC3(ADC3)-Pad26)") (class "Default")
      (node (ref "U1") (pin "26") (pinfunction "PC3(ADC3)_26") (pintype "bidirectional"))
    )
    (net (code "374") (name "unconnected-(U1-PC4(ADC4{slash}SDA)-Pad27)") (class "Default")
      (node (ref "U1") (pin "27") (pinfunction "PC4(ADC4/SDA)_27") (pintype "bidirectional"))
    )
    (net (code "375") (name "unconnected-(U1-PC5(ADC5{slash}SCL)-Pad28)") (class "Default")
      (node (ref "U1") (pin "28") (pinfunction "PC5(ADC5/SCL)_28") (pintype "bidirectional"))
    )
    (net (code "376") (name "unconnected-(U1-PD2(INT0)-Pad32)") (class "Default")
      (node (ref "U1") (pin "32") (pinfunction "PD2(INT0)_32") (pintype "bidirectional"))
    )
    (net (code "377") (name "unconnected-(U11-QH*-Pad9)") (class "Default")
      (node (ref "U11") (pin "9") (pinfunction "QH*_9") (pintype "tri_state"))
    )
  )
)
